# 03fpga.net
KiCad netlist of a schematic drawn in Altium Designer
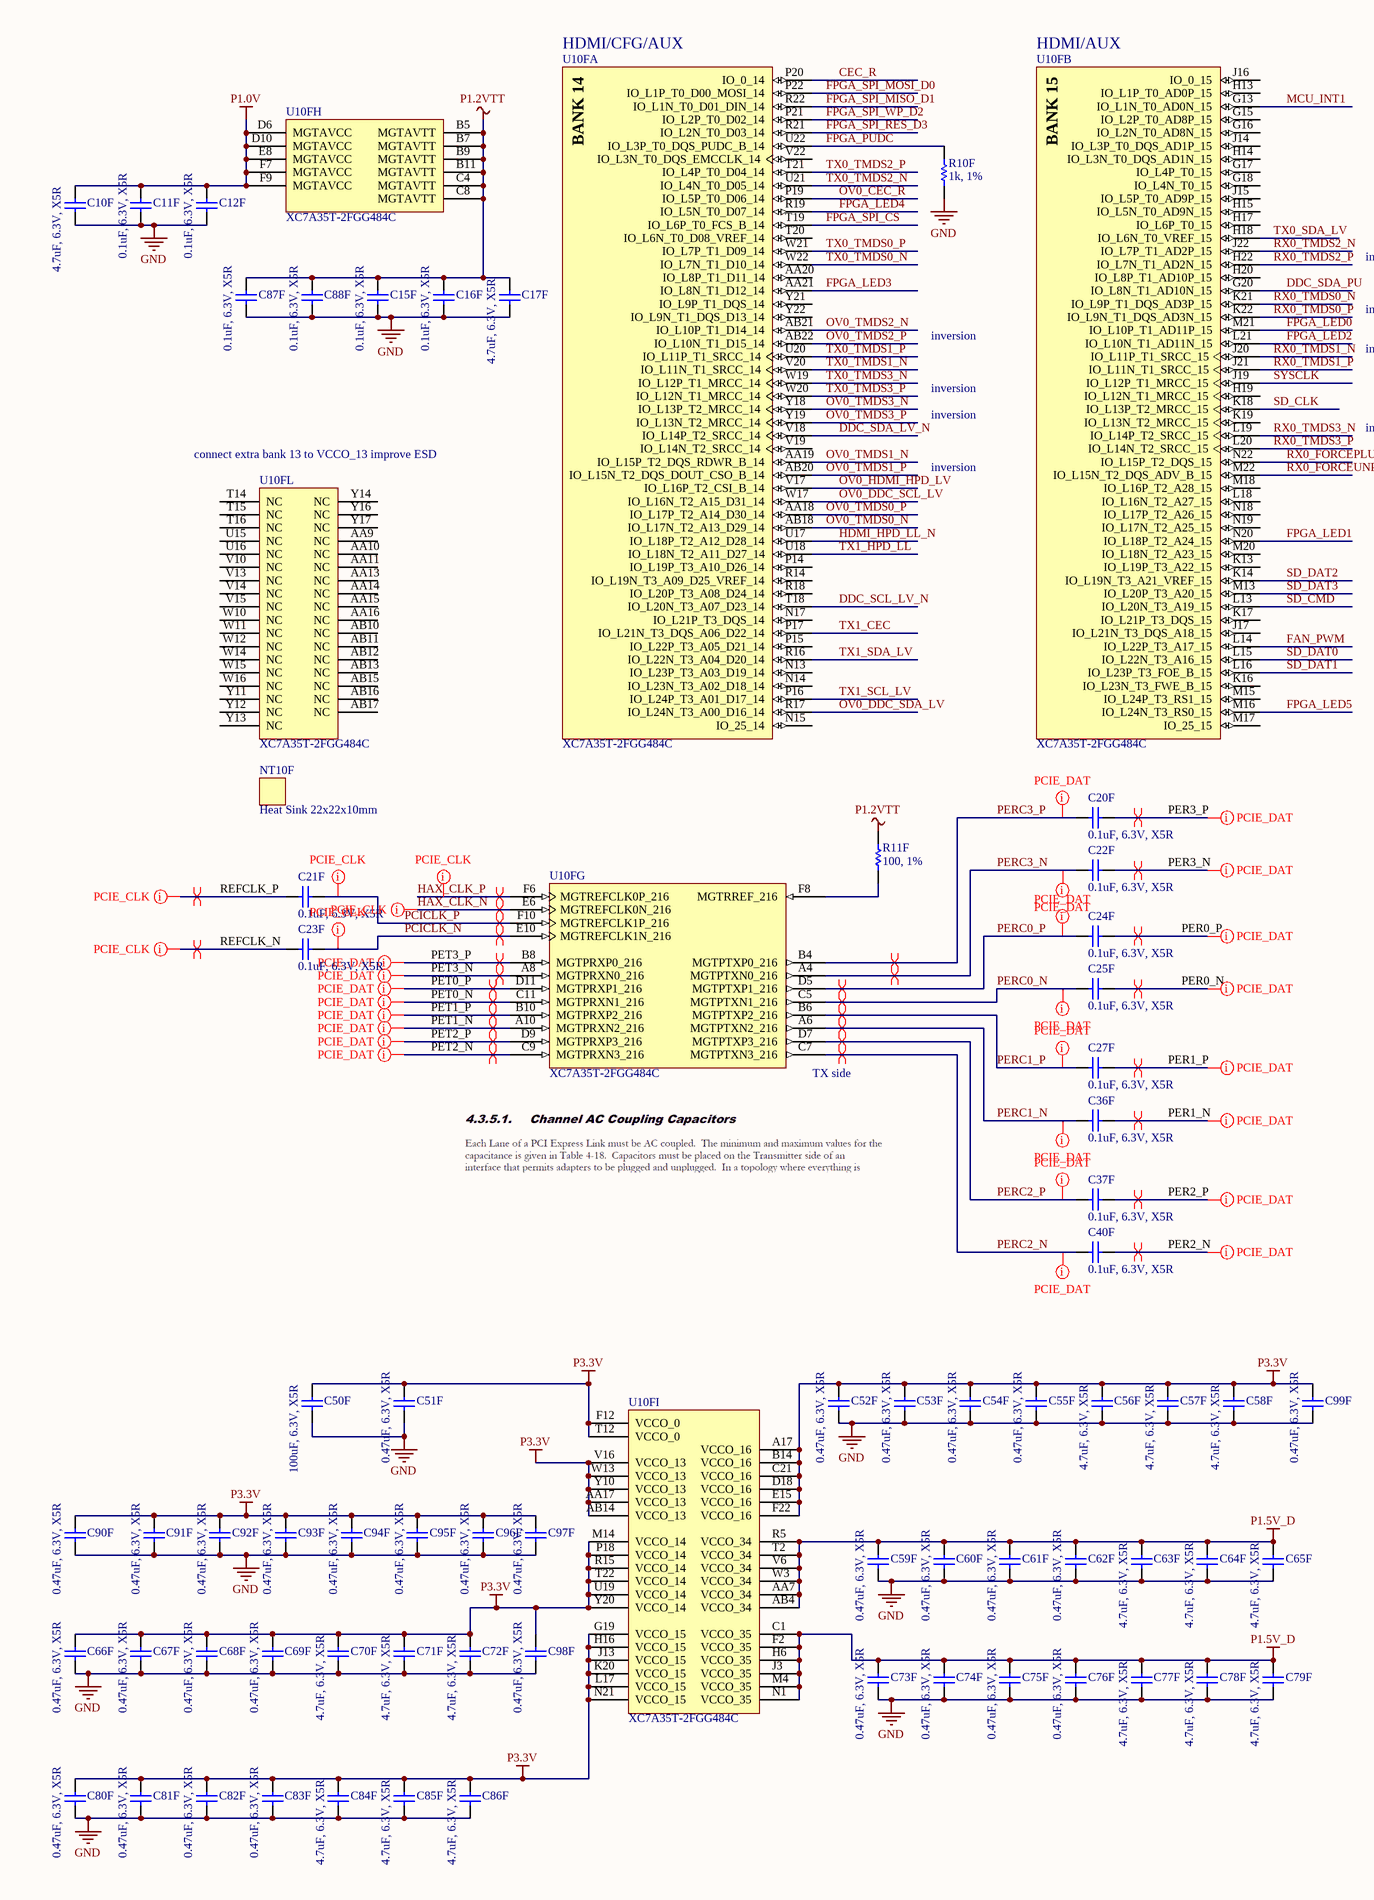
[diagram p0: 03fpga.SchDoc, left]
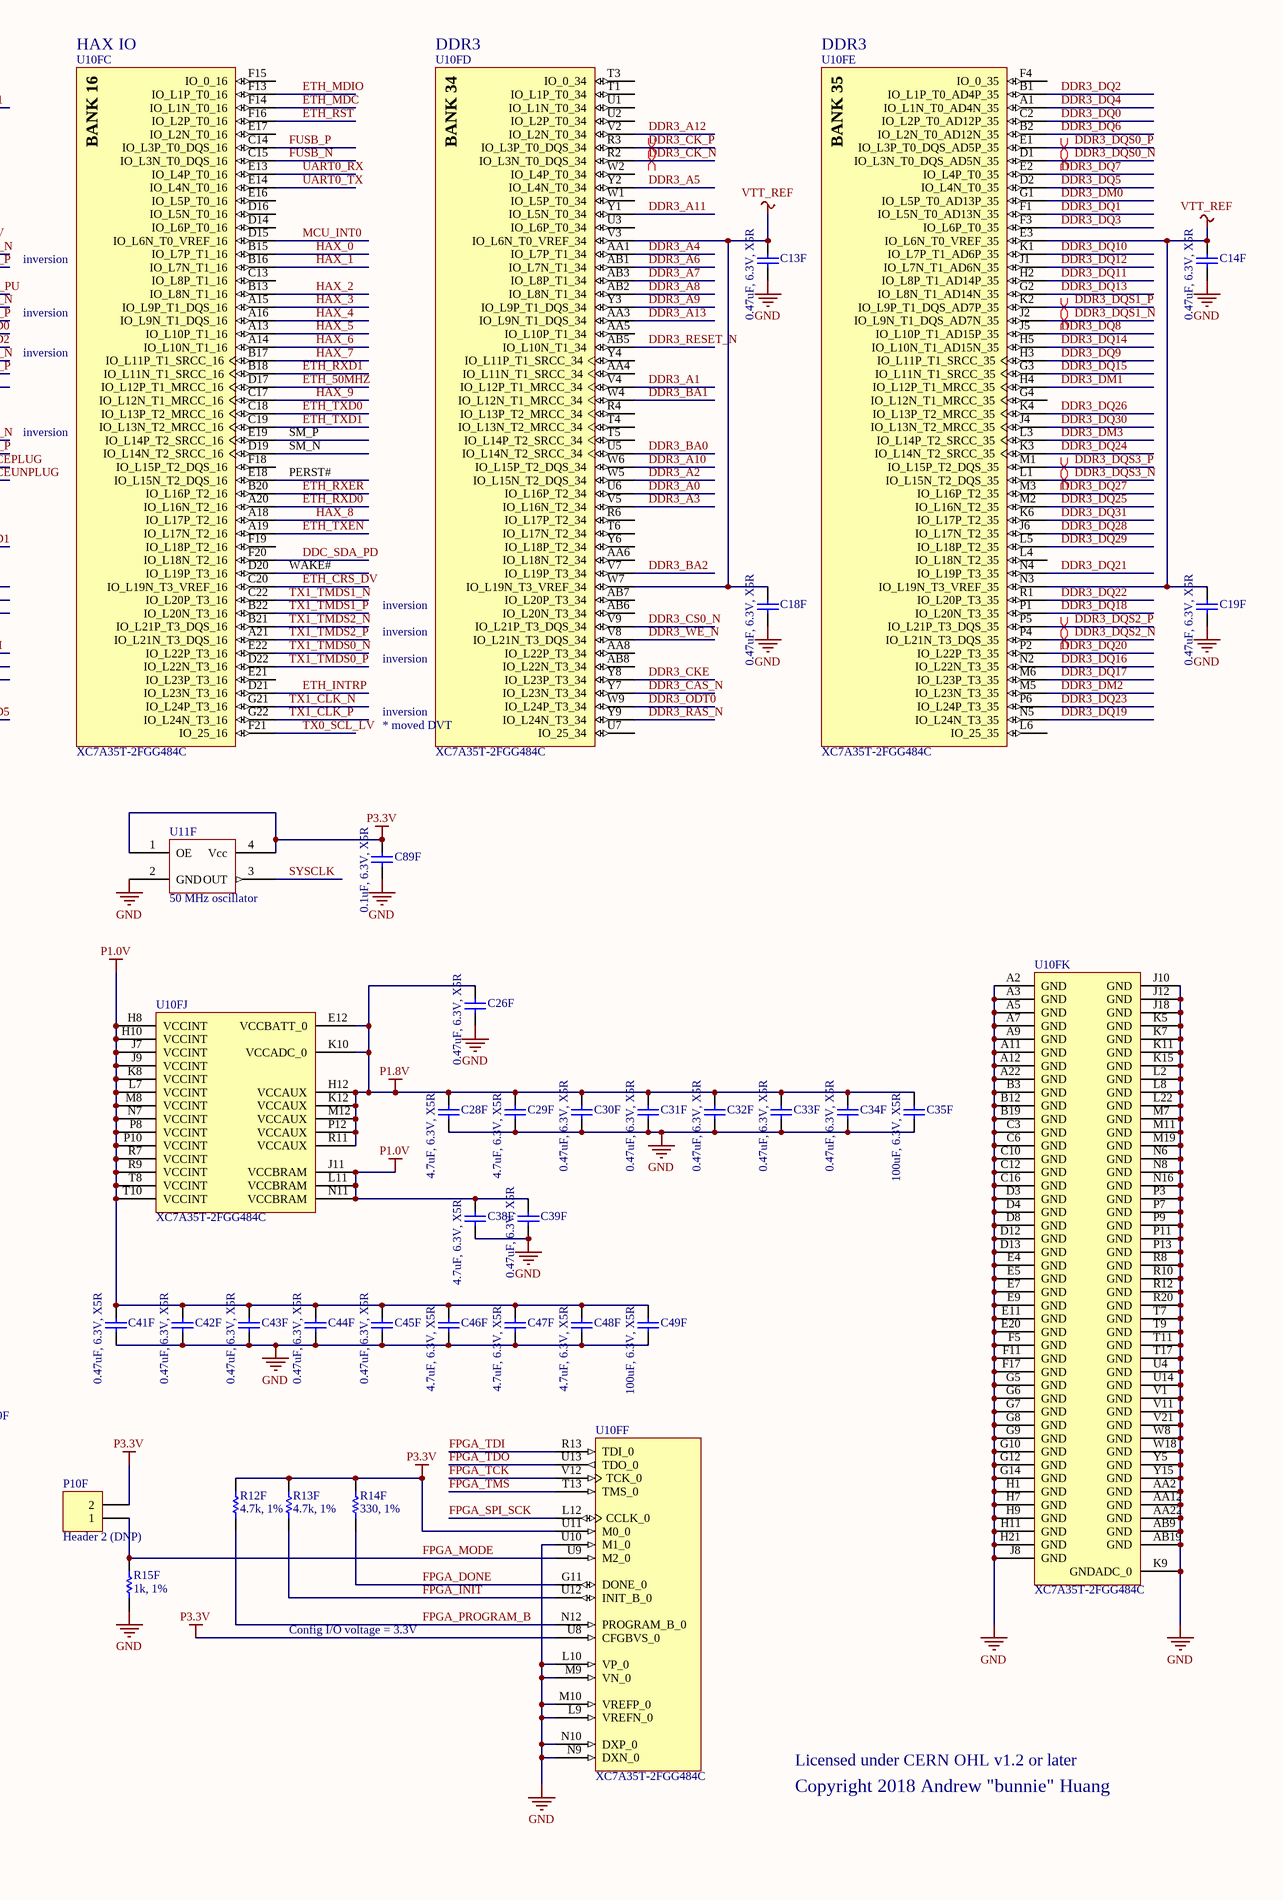
[diagram p1: 03fpga.SchDoc, right]

(export (version "E")
  (design (tool "Eeschema 10.0.6"))
  (components
    (comp (ref "C10F")
      (value "4.7uF, 6.3V, X5R")
      (footprint "CAPC1005N")
      (description "Capacitor (Semiconductor SIM Model)")
      (fields (field (name "MPN") "CL05A475MQ5NQNC"))
      (libsource (lib "Miscellaneous Devices") (part "Cap Semi"))
    )
    (comp (ref "C11F")
      (value "0.1uF, 6.3V, X5R")
      (footprint "CAPC0603X03L")
      (description "Capacitor (Semiconductor SIM Model)")
      (fields (field (name "MPN") "CL03A104KQ3NNNC"))
      (libsource (lib "Miscellaneous Devices") (part "Cap Semi"))
    )
    (comp (ref "C12F")
      (value "0.1uF, 6.3V, X5R")
      (footprint "CAPC0603X03L")
      (description "Capacitor (Semiconductor SIM Model)")
      (fields (field (name "MPN") "CL03A104KQ3NNNC"))
      (libsource (lib "Miscellaneous Devices") (part "Cap Semi"))
    )
    (comp (ref "C13F")
      (value "0.47uF, 6.3V, X5R")
      (footprint "CAPC0603X03L")
      (description "Capacitor (Semiconductor SIM Model)")
      (fields (field (name "MPN") "CL03A474KQ3NNNH"))
      (libsource (lib "Miscellaneous Devices") (part "Cap Semi"))
    )
    (comp (ref "C14F")
      (value "0.47uF, 6.3V, X5R")
      (footprint "CAPC0603X03L")
      (description "Capacitor (Semiconductor SIM Model)")
      (fields (field (name "MPN") "CL03A474KQ3NNNH"))
      (libsource (lib "Miscellaneous Devices") (part "Cap Semi"))
    )
    (comp (ref "C15F")
      (value "0.1uF, 6.3V, X5R")
      (footprint "CAPC0603X03L")
      (description "Capacitor (Semiconductor SIM Model)")
      (fields (field (name "MPN") "CL03A104KQ3NNNC"))
      (libsource (lib "Miscellaneous Devices") (part "Cap Semi"))
    )
    (comp (ref "C16F")
      (value "0.1uF, 6.3V, X5R")
      (footprint "CAPC0603X03L")
      (description "Capacitor (Semiconductor SIM Model)")
      (fields (field (name "MPN") "CL03A104KQ3NNNC"))
      (libsource (lib "Miscellaneous Devices") (part "Cap Semi"))
    )
    (comp (ref "C17F")
      (value "4.7uF, 6.3V, X5R")
      (footprint "CAPC1005N")
      (description "Capacitor (Semiconductor SIM Model)")
      (fields (field (name "MPN") "CL05A475MQ5NQNC"))
      (libsource (lib "Miscellaneous Devices") (part "Cap Semi"))
    )
    (comp (ref "C18F")
      (value "0.47uF, 6.3V, X5R")
      (footprint "CAPC0603X03L")
      (description "Capacitor (Semiconductor SIM Model)")
      (fields (field (name "MPN") "CL03A474KQ3NNNH"))
      (libsource (lib "Miscellaneous Devices") (part "Cap Semi"))
    )
    (comp (ref "C19F")
      (value "0.47uF, 6.3V, X5R")
      (footprint "CAPC0603X03L")
      (description "Capacitor (Semiconductor SIM Model)")
      (fields (field (name "MPN") "CL03A474KQ3NNNH"))
      (libsource (lib "Miscellaneous Devices") (part "Cap Semi"))
    )
    (comp (ref "C20F")
      (value "0.1uF, 6.3V, X5R")
      (footprint "CAPC0603X03L")
      (description "Capacitor (Semiconductor SIM Model)")
      (fields (field (name "MPN") "CL03A104KQ3NNNC"))
      (libsource (lib "Miscellaneous Devices") (part "Cap Semi"))
    )
    (comp (ref "C21F")
      (value "0.1uF, 6.3V, X5R")
      (footprint "CAPC0603X03L")
      (description "Capacitor (Semiconductor SIM Model)")
      (fields (field (name "MPN") "CL03A104KQ3NNNC"))
      (libsource (lib "Miscellaneous Devices") (part "Cap Semi"))
    )
    (comp (ref "C22F")
      (value "0.1uF, 6.3V, X5R")
      (footprint "CAPC0603X03L")
      (description "Capacitor (Semiconductor SIM Model)")
      (fields (field (name "MPN") "CL03A104KQ3NNNC"))
      (libsource (lib "Miscellaneous Devices") (part "Cap Semi"))
    )
    (comp (ref "C23F")
      (value "0.1uF, 6.3V, X5R")
      (footprint "CAPC0603X03L")
      (description "Capacitor (Semiconductor SIM Model)")
      (fields (field (name "MPN") "CL03A104KQ3NNNC"))
      (libsource (lib "Miscellaneous Devices") (part "Cap Semi"))
    )
    (comp (ref "C24F")
      (value "0.1uF, 6.3V, X5R")
      (footprint "CAPC0603X03L")
      (description "Capacitor (Semiconductor SIM Model)")
      (fields (field (name "MPN") "CL03A104KQ3NNNC"))
      (libsource (lib "Miscellaneous Devices") (part "Cap Semi"))
    )
    (comp (ref "C25F")
      (value "0.1uF, 6.3V, X5R")
      (footprint "CAPC0603X03L")
      (description "Capacitor (Semiconductor SIM Model)")
      (fields (field (name "MPN") "CL03A104KQ3NNNC"))
      (libsource (lib "Miscellaneous Devices") (part "Cap Semi"))
    )
    (comp (ref "C26F")
      (value "0.47uF, 6.3V, X5R")
      (footprint "CAPC0603X03L")
      (description "Capacitor (Semiconductor SIM Model)")
      (fields (field (name "MPN") "CL03A474KQ3NNNH"))
      (libsource (lib "Miscellaneous Devices") (part "Cap Semi"))
    )
    (comp (ref "C27F")
      (value "0.1uF, 6.3V, X5R")
      (footprint "CAPC0603X03L")
      (description "Capacitor (Semiconductor SIM Model)")
      (fields (field (name "MPN") "CL03A104KQ3NNNC"))
      (libsource (lib "Miscellaneous Devices") (part "Cap Semi"))
    )
    (comp (ref "C28F")
      (value "4.7uF, 6.3V, X5R")
      (footprint "CAPC1005N")
      (description "Capacitor (Semiconductor SIM Model)")
      (fields (field (name "MPN") "CL05A475MQ5NQNC"))
      (libsource (lib "Miscellaneous Devices") (part "Cap Semi"))
    )
    (comp (ref "C29F")
      (value "4.7uF, 6.3V, X5R")
      (footprint "CAPC1005N")
      (description "Capacitor (Semiconductor SIM Model)")
      (fields (field (name "MPN") "CL05A475MQ5NQNC"))
      (libsource (lib "Miscellaneous Devices") (part "Cap Semi"))
    )
    (comp (ref "C30F")
      (value "0.47uF, 6.3V, X5R")
      (footprint "CAPC0603X03L")
      (description "Capacitor (Semiconductor SIM Model)")
      (fields (field (name "MPN") "CL03A474KQ3NNNH"))
      (libsource (lib "Miscellaneous Devices") (part "Cap Semi"))
    )
    (comp (ref "C31F")
      (value "0.47uF, 6.3V, X5R")
      (footprint "CAPC0603X03L")
      (description "Capacitor (Semiconductor SIM Model)")
      (fields (field (name "MPN") "CL03A474KQ3NNNH"))
      (libsource (lib "Miscellaneous Devices") (part "Cap Semi"))
    )
    (comp (ref "C32F")
      (value "0.47uF, 6.3V, X5R")
      (footprint "CAPC0603X03L")
      (description "Capacitor (Semiconductor SIM Model)")
      (fields (field (name "MPN") "CL03A474KQ3NNNH"))
      (libsource (lib "Miscellaneous Devices") (part "Cap Semi"))
    )
    (comp (ref "C33F")
      (value "0.47uF, 6.3V, X5R")
      (footprint "CAPC0603X03L")
      (description "Capacitor (Semiconductor SIM Model)")
      (fields (field (name "MPN") "CL03A474KQ3NNNH"))
      (libsource (lib "Miscellaneous Devices") (part "Cap Semi"))
    )
    (comp (ref "C34F")
      (value "0.47uF, 6.3V, X5R")
      (footprint "CAPC0603X03L")
      (description "Capacitor (Semiconductor SIM Model)")
      (fields (field (name "MPN") "CL03A474KQ3NNNH"))
      (libsource (lib "Miscellaneous Devices") (part "Cap Semi"))
    )
    (comp (ref "C35F")
      (value "100uF, 6.3V, X5R")
      (footprint "CAPC3216N")
      (description "Capacitor (Semiconductor SIM Model)")
      (fields (field (name "MPN") "CL31A107MQHNNNE"))
      (libsource (lib "Miscellaneous Devices") (part "Cap Semi"))
    )
    (comp (ref "C36F")
      (value "0.1uF, 6.3V, X5R")
      (footprint "CAPC0603X03L")
      (description "Capacitor (Semiconductor SIM Model)")
      (fields (field (name "MPN") "CL03A104KQ3NNNC"))
      (libsource (lib "Miscellaneous Devices") (part "Cap Semi"))
    )
    (comp (ref "C37F")
      (value "0.1uF, 6.3V, X5R")
      (footprint "CAPC0603X03L")
      (description "Capacitor (Semiconductor SIM Model)")
      (fields (field (name "MPN") "CL03A104KQ3NNNC"))
      (libsource (lib "Miscellaneous Devices") (part "Cap Semi"))
    )
    (comp (ref "C38F")
      (value "4.7uF, 6.3V, X5R")
      (footprint "CAPC1005N")
      (description "Capacitor (Semiconductor SIM Model)")
      (fields (field (name "MPN") "CL05A475MQ5NQNC"))
      (libsource (lib "Miscellaneous Devices") (part "Cap Semi"))
    )
    (comp (ref "C39F")
      (value "0.47uF, 6.3V, X5R")
      (footprint "CAPC0603X03L")
      (description "Capacitor (Semiconductor SIM Model)")
      (fields (field (name "MPN") "CL03A474KQ3NNNH"))
      (libsource (lib "Miscellaneous Devices") (part "Cap Semi"))
    )
    (comp (ref "C40F")
      (value "0.1uF, 6.3V, X5R")
      (footprint "CAPC0603X03L")
      (description "Capacitor (Semiconductor SIM Model)")
      (fields (field (name "MPN") "CL03A104KQ3NNNC"))
      (libsource (lib "Miscellaneous Devices") (part "Cap Semi"))
    )
    (comp (ref "C41F")
      (value "0.47uF, 6.3V, X5R")
      (footprint "CAPC0603X03L")
      (description "Capacitor (Semiconductor SIM Model)")
      (fields (field (name "MPN") "CL03A474KQ3NNNH"))
      (libsource (lib "Miscellaneous Devices") (part "Cap Semi"))
    )
    (comp (ref "C42F")
      (value "0.47uF, 6.3V, X5R")
      (footprint "CAPC0603X03L")
      (description "Capacitor (Semiconductor SIM Model)")
      (fields (field (name "MPN") "CL03A474KQ3NNNH"))
      (libsource (lib "Miscellaneous Devices") (part "Cap Semi"))
    )
    (comp (ref "C43F")
      (value "0.47uF, 6.3V, X5R")
      (footprint "CAPC0603X03L")
      (description "Capacitor (Semiconductor SIM Model)")
      (fields (field (name "MPN") "CL03A474KQ3NNNH"))
      (libsource (lib "Miscellaneous Devices") (part "Cap Semi"))
    )
    (comp (ref "C44F")
      (value "0.47uF, 6.3V, X5R")
      (footprint "CAPC0603X03L")
      (description "Capacitor (Semiconductor SIM Model)")
      (fields (field (name "MPN") "CL03A474KQ3NNNH"))
      (libsource (lib "Miscellaneous Devices") (part "Cap Semi"))
    )
    (comp (ref "C45F")
      (value "0.47uF, 6.3V, X5R")
      (footprint "CAPC0603X03L")
      (description "Capacitor (Semiconductor SIM Model)")
      (fields (field (name "MPN") "CL03A474KQ3NNNH"))
      (libsource (lib "Miscellaneous Devices") (part "Cap Semi"))
    )
    (comp (ref "C46F")
      (value "4.7uF, 6.3V, X5R")
      (footprint "CAPC1005N")
      (description "Capacitor (Semiconductor SIM Model)")
      (fields (field (name "MPN") "CL05A475MQ5NQNC"))
      (libsource (lib "Miscellaneous Devices") (part "Cap Semi"))
    )
    (comp (ref "C47F")
      (value "4.7uF, 6.3V, X5R")
      (footprint "CAPC1005N")
      (description "Capacitor (Semiconductor SIM Model)")
      (fields (field (name "MPN") "CL05A475MQ5NQNC"))
      (libsource (lib "Miscellaneous Devices") (part "Cap Semi"))
    )
    (comp (ref "C48F")
      (value "4.7uF, 6.3V, X5R")
      (footprint "CAPC1005N")
      (description "Capacitor (Semiconductor SIM Model)")
      (fields (field (name "MPN") "CL05A475MQ5NQNC"))
      (libsource (lib "Miscellaneous Devices") (part "Cap Semi"))
    )
    (comp (ref "C49F")
      (value "100uF, 6.3V, X5R")
      (footprint "CAPC3216N")
      (description "Capacitor (Semiconductor SIM Model)")
      (fields (field (name "MPN") "CL31A107MQHNNNE"))
      (libsource (lib "Miscellaneous Devices") (part "Cap Semi"))
    )
    (comp (ref "C50F")
      (value "100uF, 6.3V, X5R")
      (footprint "CAPC3216N")
      (description "Capacitor (Semiconductor SIM Model)")
      (fields (field (name "MPN") "CL31A107MQHNNNE"))
      (libsource (lib "Miscellaneous Devices") (part "Cap Semi"))
    )
    (comp (ref "C51F")
      (value "0.47uF, 6.3V, X5R")
      (footprint "CAPC0603X03L")
      (description "Capacitor (Semiconductor SIM Model)")
      (fields (field (name "MPN") "CL03A474KQ3NNNH"))
      (libsource (lib "Miscellaneous Devices") (part "Cap Semi"))
    )
    (comp (ref "C52F")
      (value "0.47uF, 6.3V, X5R")
      (footprint "CAPC0603X03L")
      (description "Capacitor (Semiconductor SIM Model)")
      (fields (field (name "MPN") "CL03A474KQ3NNNH"))
      (libsource (lib "Miscellaneous Devices") (part "Cap Semi"))
    )
    (comp (ref "C53F")
      (value "0.47uF, 6.3V, X5R")
      (footprint "CAPC0603X03L")
      (description "Capacitor (Semiconductor SIM Model)")
      (fields (field (name "MPN") "CL03A474KQ3NNNH"))
      (libsource (lib "Miscellaneous Devices") (part "Cap Semi"))
    )
    (comp (ref "C54F")
      (value "0.47uF, 6.3V, X5R")
      (footprint "CAPC0603X03L")
      (description "Capacitor (Semiconductor SIM Model)")
      (fields (field (name "MPN") "CL03A474KQ3NNNH"))
      (libsource (lib "Miscellaneous Devices") (part "Cap Semi"))
    )
    (comp (ref "C55F")
      (value "0.47uF, 6.3V, X5R")
      (footprint "CAPC0603X03L")
      (description "Capacitor (Semiconductor SIM Model)")
      (fields (field (name "MPN") "CL03A474KQ3NNNH"))
      (libsource (lib "Miscellaneous Devices") (part "Cap Semi"))
    )
    (comp (ref "C56F")
      (value "4.7uF, 6.3V, X5R")
      (footprint "CAPC1005N")
      (description "Capacitor (Semiconductor SIM Model)")
      (fields (field (name "MPN") "CL05A475MQ5NQNC"))
      (libsource (lib "Miscellaneous Devices") (part "Cap Semi"))
    )
    (comp (ref "C57F")
      (value "4.7uF, 6.3V, X5R")
      (footprint "CAPC1005N")
      (description "Capacitor (Semiconductor SIM Model)")
      (fields (field (name "MPN") "CL05A475MQ5NQNC"))
      (libsource (lib "Miscellaneous Devices") (part "Cap Semi"))
    )
    (comp (ref "C58F")
      (value "4.7uF, 6.3V, X5R")
      (footprint "CAPC1005N")
      (description "Capacitor (Semiconductor SIM Model)")
      (fields (field (name "MPN") "CL05A475MQ5NQNC"))
      (libsource (lib "Miscellaneous Devices") (part "Cap Semi"))
    )
    (comp (ref "C59F")
      (value "0.47uF, 6.3V, X5R")
      (footprint "CAPC0603X03L")
      (description "Capacitor (Semiconductor SIM Model)")
      (fields (field (name "MPN") "CL03A474KQ3NNNH"))
      (libsource (lib "Miscellaneous Devices") (part "Cap Semi"))
    )
    (comp (ref "C60F")
      (value "0.47uF, 6.3V, X5R")
      (footprint "CAPC0603X03L")
      (description "Capacitor (Semiconductor SIM Model)")
      (fields (field (name "MPN") "CL03A474KQ3NNNH"))
      (libsource (lib "Miscellaneous Devices") (part "Cap Semi"))
    )
    (comp (ref "C61F")
      (value "0.47uF, 6.3V, X5R")
      (footprint "CAPC0603X03L")
      (description "Capacitor (Semiconductor SIM Model)")
      (fields (field (name "MPN") "CL03A474KQ3NNNH"))
      (libsource (lib "Miscellaneous Devices") (part "Cap Semi"))
    )
    (comp (ref "C62F")
      (value "0.47uF, 6.3V, X5R")
      (footprint "CAPC0603X03L")
      (description "Capacitor (Semiconductor SIM Model)")
      (fields (field (name "MPN") "CL03A474KQ3NNNH"))
      (libsource (lib "Miscellaneous Devices") (part "Cap Semi"))
    )
    (comp (ref "C63F")
      (value "4.7uF, 6.3V, X5R")
      (footprint "CAPC1005N")
      (description "Capacitor (Semiconductor SIM Model)")
      (fields (field (name "MPN") "CL05A475MQ5NQNC"))
      (libsource (lib "Miscellaneous Devices") (part "Cap Semi"))
    )
    (comp (ref "C64F")
      (value "4.7uF, 6.3V, X5R")
      (footprint "CAPC1005N")
      (description "Capacitor (Semiconductor SIM Model)")
      (fields (field (name "MPN") "CL05A475MQ5NQNC"))
      (libsource (lib "Miscellaneous Devices") (part "Cap Semi"))
    )
    (comp (ref "C65F")
      (value "4.7uF, 6.3V, X5R")
      (footprint "CAPC1005N")
      (description "Capacitor (Semiconductor SIM Model)")
      (fields (field (name "MPN") "CL05A475MQ5NQNC"))
      (libsource (lib "Miscellaneous Devices") (part "Cap Semi"))
    )
    (comp (ref "C66F")
      (value "0.47uF, 6.3V, X5R")
      (footprint "CAPC0603X03L")
      (description "Capacitor (Semiconductor SIM Model)")
      (fields (field (name "MPN") "CL03A474KQ3NNNH"))
      (libsource (lib "Miscellaneous Devices") (part "Cap Semi"))
    )
    (comp (ref "C67F")
      (value "0.47uF, 6.3V, X5R")
      (footprint "CAPC0603X03L")
      (description "Capacitor (Semiconductor SIM Model)")
      (fields (field (name "MPN") "CL03A474KQ3NNNH"))
      (libsource (lib "Miscellaneous Devices") (part "Cap Semi"))
    )
    (comp (ref "C68F")
      (value "0.47uF, 6.3V, X5R")
      (footprint "CAPC0603X03L")
      (description "Capacitor (Semiconductor SIM Model)")
      (fields (field (name "MPN") "CL03A474KQ3NNNH"))
      (libsource (lib "Miscellaneous Devices") (part "Cap Semi"))
    )
    (comp (ref "C69F")
      (value "0.47uF, 6.3V, X5R")
      (footprint "CAPC0603X03L")
      (description "Capacitor (Semiconductor SIM Model)")
      (fields (field (name "MPN") "CL03A474KQ3NNNH"))
      (libsource (lib "Miscellaneous Devices") (part "Cap Semi"))
    )
    (comp (ref "C70F")
      (value "4.7uF, 6.3V, X5R")
      (footprint "CAPC1005N")
      (description "Capacitor (Semiconductor SIM Model)")
      (fields (field (name "MPN") "CL05A475MQ5NQNC"))
      (libsource (lib "Miscellaneous Devices") (part "Cap Semi"))
    )
    (comp (ref "C71F")
      (value "4.7uF, 6.3V, X5R")
      (footprint "CAPC1005N")
      (description "Capacitor (Semiconductor SIM Model)")
      (fields (field (name "MPN") "CL05A475MQ5NQNC"))
      (libsource (lib "Miscellaneous Devices") (part "Cap Semi"))
    )
    (comp (ref "C72F")
      (value "4.7uF, 6.3V, X5R")
      (footprint "CAPC1005N")
      (description "Capacitor (Semiconductor SIM Model)")
      (fields (field (name "MPN") "CL05A475MQ5NQNC"))
      (libsource (lib "Miscellaneous Devices") (part "Cap Semi"))
    )
    (comp (ref "C73F")
      (value "0.47uF, 6.3V, X5R")
      (footprint "CAPC0603X03L")
      (description "Capacitor (Semiconductor SIM Model)")
      (fields (field (name "MPN") "CL03A474KQ3NNNH"))
      (libsource (lib "Miscellaneous Devices") (part "Cap Semi"))
    )
    (comp (ref "C74F")
      (value "0.47uF, 6.3V, X5R")
      (footprint "CAPC0603X03L")
      (description "Capacitor (Semiconductor SIM Model)")
      (fields (field (name "MPN") "CL03A474KQ3NNNH"))
      (libsource (lib "Miscellaneous Devices") (part "Cap Semi"))
    )
    (comp (ref "C75F")
      (value "0.47uF, 6.3V, X5R")
      (footprint "CAPC0603X03L")
      (description "Capacitor (Semiconductor SIM Model)")
      (fields (field (name "MPN") "CL03A474KQ3NNNH"))
      (libsource (lib "Miscellaneous Devices") (part "Cap Semi"))
    )
    (comp (ref "C76F")
      (value "0.47uF, 6.3V, X5R")
      (footprint "CAPC0603X03L")
      (description "Capacitor (Semiconductor SIM Model)")
      (fields (field (name "MPN") "CL03A474KQ3NNNH"))
      (libsource (lib "Miscellaneous Devices") (part "Cap Semi"))
    )
    (comp (ref "C77F")
      (value "4.7uF, 6.3V, X5R")
      (footprint "CAPC1005N")
      (description "Capacitor (Semiconductor SIM Model)")
      (fields (field (name "MPN") "CL05A475MQ5NQNC"))
      (libsource (lib "Miscellaneous Devices") (part "Cap Semi"))
    )
    (comp (ref "C78F")
      (value "4.7uF, 6.3V, X5R")
      (footprint "CAPC1005N")
      (description "Capacitor (Semiconductor SIM Model)")
      (fields (field (name "MPN") "CL05A475MQ5NQNC"))
      (libsource (lib "Miscellaneous Devices") (part "Cap Semi"))
    )
    (comp (ref "C79F")
      (value "4.7uF, 6.3V, X5R")
      (footprint "CAPC1005N")
      (description "Capacitor (Semiconductor SIM Model)")
      (fields (field (name "MPN") "CL05A475MQ5NQNC"))
      (libsource (lib "Miscellaneous Devices") (part "Cap Semi"))
    )
    (comp (ref "C80F")
      (value "0.47uF, 6.3V, X5R")
      (footprint "CAPC0603X03L")
      (description "Capacitor (Semiconductor SIM Model)")
      (fields (field (name "MPN") "CL03A474KQ3NNNH"))
      (libsource (lib "Miscellaneous Devices") (part "Cap Semi"))
    )
    (comp (ref "C81F")
      (value "0.47uF, 6.3V, X5R")
      (footprint "CAPC0603X03L")
      (description "Capacitor (Semiconductor SIM Model)")
      (fields (field (name "MPN") "CL03A474KQ3NNNH"))
      (libsource (lib "Miscellaneous Devices") (part "Cap Semi"))
    )
    (comp (ref "C82F")
      (value "0.47uF, 6.3V, X5R")
      (footprint "CAPC0603X03L")
      (description "Capacitor (Semiconductor SIM Model)")
      (fields (field (name "MPN") "CL03A474KQ3NNNH"))
      (libsource (lib "Miscellaneous Devices") (part "Cap Semi"))
    )
    (comp (ref "C83F")
      (value "0.47uF, 6.3V, X5R")
      (footprint "CAPC0603X03L")
      (description "Capacitor (Semiconductor SIM Model)")
      (fields (field (name "MPN") "CL03A474KQ3NNNH"))
      (libsource (lib "Miscellaneous Devices") (part "Cap Semi"))
    )
    (comp (ref "C84F")
      (value "4.7uF, 6.3V, X5R")
      (footprint "CAPC1005N")
      (description "Capacitor (Semiconductor SIM Model)")
      (fields (field (name "MPN") "CL05A475MQ5NQNC"))
      (libsource (lib "Miscellaneous Devices") (part "Cap Semi"))
    )
    (comp (ref "C85F")
      (value "4.7uF, 6.3V, X5R")
      (footprint "CAPC1005N")
      (description "Capacitor (Semiconductor SIM Model)")
      (fields (field (name "MPN") "CL05A475MQ5NQNC"))
      (libsource (lib "Miscellaneous Devices") (part "Cap Semi"))
    )
    (comp (ref "C86F")
      (value "4.7uF, 6.3V, X5R")
      (footprint "CAPC1005N")
      (description "Capacitor (Semiconductor SIM Model)")
      (fields (field (name "MPN") "CL05A475MQ5NQNC"))
      (libsource (lib "Miscellaneous Devices") (part "Cap Semi"))
    )
    (comp (ref "C87F")
      (value "0.1uF, 6.3V, X5R")
      (footprint "CAPC0603X03L")
      (description "Capacitor (Semiconductor SIM Model)")
      (fields (field (name "MPN") "CL03A104KQ3NNNC"))
      (libsource (lib "Miscellaneous Devices") (part "Cap Semi"))
    )
    (comp (ref "C88F")
      (value "0.1uF, 6.3V, X5R")
      (footprint "CAPC0603X03L")
      (description "Capacitor (Semiconductor SIM Model)")
      (fields (field (name "MPN") "CL03A104KQ3NNNC"))
      (libsource (lib "Miscellaneous Devices") (part "Cap Semi"))
    )
    (comp (ref "C89F")
      (value "0.1uF, 6.3V, X5R")
      (footprint "CAPC0603X03L")
      (description "Capacitor (Semiconductor SIM Model)")
      (fields (field (name "MPN") "CL03A104KQ3NNNC"))
      (libsource (lib "Miscellaneous Devices") (part "Cap Semi"))
    )
    (comp (ref "C90F")
      (value "0.47uF, 6.3V, X5R")
      (footprint "CAPC0603X03L")
      (description "Capacitor (Semiconductor SIM Model)")
      (fields (field (name "MPN") "CL03A474KQ3NNNH"))
      (libsource (lib "Miscellaneous Devices") (part "Cap Semi"))
    )
    (comp (ref "C91F")
      (value "0.47uF, 6.3V, X5R")
      (footprint "CAPC0603X03L")
      (description "Capacitor (Semiconductor SIM Model)")
      (fields (field (name "MPN") "CL03A474KQ3NNNH"))
      (libsource (lib "Miscellaneous Devices") (part "Cap Semi"))
    )
    (comp (ref "C92F")
      (value "0.47uF, 6.3V, X5R")
      (footprint "CAPC0603X03L")
      (description "Capacitor (Semiconductor SIM Model)")
      (fields (field (name "MPN") "CL03A474KQ3NNNH"))
      (libsource (lib "Miscellaneous Devices") (part "Cap Semi"))
    )
    (comp (ref "C93F")
      (value "0.47uF, 6.3V, X5R")
      (footprint "CAPC0603X03L")
      (description "Capacitor (Semiconductor SIM Model)")
      (fields (field (name "MPN") "CL03A474KQ3NNNH"))
      (libsource (lib "Miscellaneous Devices") (part "Cap Semi"))
    )
    (comp (ref "C94F")
      (value "0.47uF, 6.3V, X5R")
      (footprint "CAPC0603X03L")
      (description "Capacitor (Semiconductor SIM Model)")
      (fields (field (name "MPN") "CL03A474KQ3NNNH"))
      (libsource (lib "Miscellaneous Devices") (part "Cap Semi"))
    )
    (comp (ref "C95F")
      (value "0.47uF, 6.3V, X5R")
      (footprint "CAPC0603X03L")
      (description "Capacitor (Semiconductor SIM Model)")
      (fields (field (name "MPN") "CL03A474KQ3NNNH"))
      (libsource (lib "Miscellaneous Devices") (part "Cap Semi"))
    )
    (comp (ref "C96F")
      (value "0.47uF, 6.3V, X5R")
      (footprint "CAPC0603X03L")
      (description "Capacitor (Semiconductor SIM Model)")
      (fields (field (name "MPN") "CL03A474KQ3NNNH"))
      (libsource (lib "Miscellaneous Devices") (part "Cap Semi"))
    )
    (comp (ref "C97F")
      (value "0.47uF, 6.3V, X5R")
      (footprint "CAPC0603X03L")
      (description "Capacitor (Semiconductor SIM Model)")
      (fields (field (name "MPN") "CL03A474KQ3NNNH"))
      (libsource (lib "Miscellaneous Devices") (part "Cap Semi"))
    )
    (comp (ref "C98F")
      (value "0.47uF, 6.3V, X5R")
      (footprint "CAPC0603X03L")
      (description "Capacitor (Semiconductor SIM Model)")
      (fields (field (name "MPN") "CL03A474KQ3NNNH"))
      (libsource (lib "Miscellaneous Devices") (part "Cap Semi"))
    )
    (comp (ref "C99F")
      (value "0.47uF, 6.3V, X5R")
      (footprint "CAPC0603X03L")
      (description "Capacitor (Semiconductor SIM Model)")
      (fields (field (name "MPN") "CL03A474KQ3NNNH"))
      (libsource (lib "Miscellaneous Devices") (part "Cap Semi"))
    )
    (comp (ref "NT10F")
      (value "Heat Sink 22x22x10mm")
      (description "Placeholder for non-board BOM items")
      (fields (field (name "MPN") "22x22x10mm heat sink + double tape"))
      (libsource (lib "commonsch") (part "NOTE"))
    )
    (comp (ref "P10F")
      (value "Header 2 (DNP)")
      (footprint "HDR1X2")
      (description "Header, 2-Pin")
      (fields (field (name "MPN") "DNP") (field (name "PUBLISHER") "Altium Limited"))
      (libsource (lib "Miscellaneous Connectors") (part "Header 2"))
    )
    (comp (ref "R10F")
      (value "1k, 1%")
      (footprint "RESC1005N")
      (description "Resistor")
      (fields (field (name "MPN") "RS02U102FT"))
      (libsource (lib "Miscellaneous Devices") (part "Res1"))
    )
    (comp (ref "R11F")
      (value "100, 1%")
      (footprint "RESC1005N")
      (description "Resistor")
      (fields (field (name "MPN") "ANY"))
      (libsource (lib "Miscellaneous Devices") (part "Res1"))
    )
    (comp (ref "R12F")
      (value "4.7k, 1%")
      (footprint "RESC1005N")
      (description "Resistor")
      (fields (field (name "MPN") "ANY"))
      (libsource (lib "Miscellaneous Devices") (part "Res1"))
    )
    (comp (ref "R13F")
      (value "4.7k, 1%")
      (footprint "RESC1005N")
      (description "Resistor")
      (fields (field (name "MPN") "ANY"))
      (libsource (lib "Miscellaneous Devices") (part "Res1"))
    )
    (comp (ref "R14F")
      (value "330, 1%")
      (footprint "RESC1005N")
      (description "Resistor")
      (fields (field (name "MPN") "RS02U331FT"))
      (libsource (lib "Miscellaneous Devices") (part "Res1"))
    )
    (comp (ref "R15F")
      (value "1k, 1%")
      (footprint "RESC1005N")
      (description "Resistor")
      (fields (field (name "MPN") "RS02U102FT"))
      (libsource (lib "Miscellaneous Devices") (part "Res1"))
    )
    (comp (ref "U10F")
      (value "XC7A35T-2FGG484C")
      (footprint "FGG484")
      (description "Artix-7 FPGA, 250 User I/Os, 4 GTP, 484-Ball BGA, Speed Grade 2, Commercial Grade, Pb-Free")
      (fields (field (name "MANUFACTURER") "Xilinx"))
      (libsource (lib "Xilinx Artix-7") (part "XC7A35T-2FGG484C"))
    )
    (comp (ref "U11F")
      (value "50 MHz oscillator")
      (footprint "ABRACON_ASDMB")
      (description "Abracon ASDMB Miniature Oscillator")
      (fields (field (name "MPN") "ASDMB-50.000MHZ-LC-T"))
      (libsource (lib "commonsch") (part "OSCILLATOR"))
    )
  )
  (nets
    (net (code "1") (name "/CEC_R") (class "Default")
      (node (ref "U10F") (pin "P20") (pinfunction "IO_0_14_P20") (pintype "bidirectional"))
    )
    (net (code "2") (name "/DDC_SCL_LV_N") (class "Default")
      (node (ref "U10F") (pin "T18") (pinfunction "IO_L20N_T3_A07_D23_14_T18") (pintype "bidirectional"))
    )
    (net (code "3") (name "/DDC_SDA_LV_N") (class "Default")
      (node (ref "U10F") (pin "V18") (pinfunction "IO_L14P_T2_SRCC_14_V18") (pintype "bidirectional"))
    )
    (net (code "4") (name "/DDC_SDA_PD") (class "Default")
      (node (ref "U10F") (pin "F20") (pinfunction "IO_L18N_T2_16_F20") (pintype "bidirectional"))
    )
    (net (code "5") (name "/DDC_SDA_PU") (class "Default")
      (node (ref "U10F") (pin "G20") (pinfunction "IO_L8N_T1_AD10N_15_G20") (pintype "bidirectional"))
    )
    (net (code "6") (name "/DDR3_A0") (class "Default")
      (node (ref "U10F") (pin "U6") (pinfunction "IO_L16P_T2_34_U6") (pintype "bidirectional"))
    )
    (net (code "7") (name "/DDR3_A1") (class "Default")
      (node (ref "U10F") (pin "V4") (pinfunction "IO_L12P_T1_MRCC_34_V4") (pintype "bidirectional"))
    )
    (net (code "8") (name "/DDR3_A2") (class "Default")
      (node (ref "U10F") (pin "W5") (pinfunction "IO_L15N_T2_DQS_34_W5") (pintype "bidirectional"))
    )
    (net (code "9") (name "/DDR3_A3") (class "Default")
      (node (ref "U10F") (pin "V5") (pinfunction "IO_L16N_T2_34_V5") (pintype "bidirectional"))
    )
    (net (code "10") (name "/DDR3_A4") (class "Default")
      (node (ref "U10F") (pin "AA1") (pinfunction "IO_L7P_T1_34_AA1") (pintype "bidirectional"))
    )
    (net (code "11") (name "/DDR3_A5") (class "Default")
      (node (ref "U10F") (pin "Y2") (pinfunction "IO_L4N_T0_34_Y2") (pintype "bidirectional"))
    )
    (net (code "12") (name "/DDR3_A6") (class "Default")
      (node (ref "U10F") (pin "AB1") (pinfunction "IO_L7N_T1_34_AB1") (pintype "bidirectional"))
    )
    (net (code "13") (name "/DDR3_A7") (class "Default")
      (node (ref "U10F") (pin "AB3") (pinfunction "IO_L8P_T1_34_AB3") (pintype "bidirectional"))
    )
    (net (code "14") (name "/DDR3_A8") (class "Default")
      (node (ref "U10F") (pin "AB2") (pinfunction "IO_L8N_T1_34_AB2") (pintype "bidirectional"))
    )
    (net (code "15") (name "/DDR3_A9") (class "Default")
      (node (ref "U10F") (pin "Y3") (pinfunction "IO_L9P_T1_DQS_34_Y3") (pintype "bidirectional"))
    )
    (net (code "16") (name "/DDR3_A10") (class "Default")
      (node (ref "U10F") (pin "W6") (pinfunction "IO_L15P_T2_DQS_34_W6") (pintype "bidirectional"))
    )
    (net (code "17") (name "/DDR3_A11") (class "Default")
      (node (ref "U10F") (pin "Y1") (pinfunction "IO_L5N_T0_34_Y1") (pintype "bidirectional"))
    )
    (net (code "18") (name "/DDR3_A12") (class "Default")
      (node (ref "U10F") (pin "V2") (pinfunction "IO_L2N_T0_34_V2") (pintype "bidirectional"))
    )
    (net (code "19") (name "/DDR3_A13") (class "Default")
      (node (ref "U10F") (pin "AA3") (pinfunction "IO_L9N_T1_DQS_34_AA3") (pintype "bidirectional"))
    )
    (net (code "20") (name "/DDR3_BA0") (class "Default")
      (node (ref "U10F") (pin "U5") (pinfunction "IO_L14N_T2_SRCC_34_U5") (pintype "bidirectional"))
    )
    (net (code "21") (name "/DDR3_BA1") (class "Default")
      (node (ref "U10F") (pin "W4") (pinfunction "IO_L12N_T1_MRCC_34_W4") (pintype "bidirectional"))
    )
    (net (code "22") (name "/DDR3_BA2") (class "Default")
      (node (ref "U10F") (pin "V7") (pinfunction "IO_L19P_T3_34_V7") (pintype "bidirectional"))
    )
    (net (code "23") (name "/DDR3_CAS_N") (class "Default")
      (node (ref "U10F") (pin "Y7") (pinfunction "IO_L23N_T3_34_Y7") (pintype "bidirectional"))
    )
    (net (code "24") (name "/DDR3_CKE") (class "Default")
      (node (ref "U10F") (pin "Y8") (pinfunction "IO_L23P_T3_34_Y8") (pintype "bidirectional"))
    )
    (net (code "25") (name "/DDR3_CK_N") (class "Default")
      (node (ref "U10F") (pin "R2") (pinfunction "IO_L3N_T0_DQS_34_R2") (pintype "bidirectional"))
    )
    (net (code "26") (name "/DDR3_CK_P") (class "Default")
      (node (ref "U10F") (pin "R3") (pinfunction "IO_L3P_T0_DQS_34_R3") (pintype "bidirectional"))
    )
    (net (code "27") (name "/DDR3_CS0_N") (class "Default")
      (node (ref "U10F") (pin "V9") (pinfunction "IO_L21P_T3_DQS_34_V9") (pintype "bidirectional"))
    )
    (net (code "28") (name "/DDR3_DM0") (class "Default")
      (node (ref "U10F") (pin "G1") (pinfunction "IO_L5P_T0_AD13P_35_G1") (pintype "bidirectional"))
    )
    (net (code "29") (name "/DDR3_DM1") (class "Default")
      (node (ref "U10F") (pin "H4") (pinfunction "IO_L12P_T1_MRCC_35_H4") (pintype "bidirectional"))
    )
    (net (code "30") (name "/DDR3_DM2") (class "Default")
      (node (ref "U10F") (pin "M5") (pinfunction "IO_L23N_T3_35_M5") (pintype "bidirectional"))
    )
    (net (code "31") (name "/DDR3_DM3") (class "Default")
      (node (ref "U10F") (pin "L3") (pinfunction "IO_L14P_T2_SRCC_35_L3") (pintype "bidirectional"))
    )
    (net (code "32") (name "/DDR3_DQ0") (class "Default")
      (node (ref "U10F") (pin "C2") (pinfunction "IO_L2P_T0_AD12P_35_C2") (pintype "bidirectional"))
    )
    (net (code "33") (name "/DDR3_DQ1") (class "Default")
      (node (ref "U10F") (pin "F1") (pinfunction "IO_L5N_T0_AD13N_35_F1") (pintype "bidirectional"))
    )
    (net (code "34") (name "/DDR3_DQ2") (class "Default")
      (node (ref "U10F") (pin "B1") (pinfunction "IO_L1P_T0_AD4P_35_B1") (pintype "bidirectional"))
    )
    (net (code "35") (name "/DDR3_DQ3") (class "Default")
      (node (ref "U10F") (pin "F3") (pinfunction "IO_L6P_T0_35_F3") (pintype "bidirectional"))
    )
    (net (code "36") (name "/DDR3_DQ4") (class "Default")
      (node (ref "U10F") (pin "A1") (pinfunction "IO_L1N_T0_AD4N_35_A1") (pintype "bidirectional"))
    )
    (net (code "37") (name "/DDR3_DQ5") (class "Default")
      (node (ref "U10F") (pin "D2") (pinfunction "IO_L4N_T0_35_D2") (pintype "bidirectional"))
    )
    (net (code "38") (name "/DDR3_DQ6") (class "Default")
      (node (ref "U10F") (pin "B2") (pinfunction "IO_L2N_T0_AD12N_35_B2") (pintype "bidirectional"))
    )
    (net (code "39") (name "/DDR3_DQ7") (class "Default")
      (node (ref "U10F") (pin "E2") (pinfunction "IO_L4P_T0_35_E2") (pintype "bidirectional"))
    )
    (net (code "40") (name "/DDR3_DQ8") (class "Default")
      (node (ref "U10F") (pin "J5") (pinfunction "IO_L10P_T1_AD15P_35_J5") (pintype "bidirectional"))
    )
    (net (code "41") (name "/DDR3_DQ9") (class "Default")
      (node (ref "U10F") (pin "H3") (pinfunction "IO_L11P_T1_SRCC_35_H3") (pintype "bidirectional"))
    )
    (net (code "42") (name "/DDR3_DQ10") (class "Default")
      (node (ref "U10F") (pin "K1") (pinfunction "IO_L7P_T1_AD6P_35_K1") (pintype "bidirectional"))
    )
    (net (code "43") (name "/DDR3_DQ11") (class "Default")
      (node (ref "U10F") (pin "H2") (pinfunction "IO_L8P_T1_AD14P_35_H2") (pintype "bidirectional"))
    )
    (net (code "44") (name "/DDR3_DQ12") (class "Default")
      (node (ref "U10F") (pin "J1") (pinfunction "IO_L7N_T1_AD6N_35_J1") (pintype "bidirectional"))
    )
    (net (code "45") (name "/DDR3_DQ13") (class "Default")
      (node (ref "U10F") (pin "G2") (pinfunction "IO_L8N_T1_AD14N_35_G2") (pintype "bidirectional"))
    )
    (net (code "46") (name "/DDR3_DQ14") (class "Default")
      (node (ref "U10F") (pin "H5") (pinfunction "IO_L10N_T1_AD15N_35_H5") (pintype "bidirectional"))
    )
    (net (code "47") (name "/DDR3_DQ15") (class "Default")
      (node (ref "U10F") (pin "G3") (pinfunction "IO_L11N_T1_SRCC_35_G3") (pintype "bidirectional"))
    )
    (net (code "48") (name "/DDR3_DQ16") (class "Default")
      (node (ref "U10F") (pin "N2") (pinfunction "IO_L22N_T3_35_N2") (pintype "bidirectional"))
    )
    (net (code "49") (name "/DDR3_DQ17") (class "Default")
      (node (ref "U10F") (pin "M6") (pinfunction "IO_L23P_T3_35_M6") (pintype "bidirectional"))
    )
    (net (code "50") (name "/DDR3_DQ18") (class "Default")
      (node (ref "U10F") (pin "P1") (pinfunction "IO_L20N_T3_35_P1") (pintype "bidirectional"))
    )
    (net (code "51") (name "/DDR3_DQ19") (class "Default")
      (node (ref "U10F") (pin "N5") (pinfunction "IO_L24N_T3_35_N5") (pintype "bidirectional"))
    )
    (net (code "52") (name "/DDR3_DQ20") (class "Default")
      (node (ref "U10F") (pin "P2") (pinfunction "IO_L22P_T3_35_P2") (pintype "bidirectional"))
    )
    (net (code "53") (name "/DDR3_DQ21") (class "Default")
      (node (ref "U10F") (pin "N4") (pinfunction "IO_L19P_T3_35_N4") (pintype "bidirectional"))
    )
    (net (code "54") (name "/DDR3_DQ22") (class "Default")
      (node (ref "U10F") (pin "R1") (pinfunction "IO_L20P_T3_35_R1") (pintype "bidirectional"))
    )
    (net (code "55") (name "/DDR3_DQ23") (class "Default")
      (node (ref "U10F") (pin "P6") (pinfunction "IO_L24P_T3_35_P6") (pintype "bidirectional"))
    )
    (net (code "56") (name "/DDR3_DQ24") (class "Default")
      (node (ref "U10F") (pin "K3") (pinfunction "IO_L14N_T2_SRCC_35_K3") (pintype "bidirectional"))
    )
    (net (code "57") (name "/DDR3_DQ25") (class "Default")
      (node (ref "U10F") (pin "M2") (pinfunction "IO_L16N_T2_35_M2") (pintype "bidirectional"))
    )
    (net (code "58") (name "/DDR3_DQ26") (class "Default")
      (node (ref "U10F") (pin "K4") (pinfunction "IO_L13P_T2_MRCC_35_K4") (pintype "bidirectional"))
    )
    (net (code "59") (name "/DDR3_DQ27") (class "Default")
      (node (ref "U10F") (pin "M3") (pinfunction "IO_L16P_T2_35_M3") (pintype "bidirectional"))
    )
    (net (code "60") (name "/DDR3_DQ28") (class "Default")
      (node (ref "U10F") (pin "J6") (pinfunction "IO_L17N_T2_35_J6") (pintype "bidirectional"))
    )
    (net (code "61") (name "/DDR3_DQ29") (class "Default")
      (node (ref "U10F") (pin "L5") (pinfunction "IO_L18P_T2_35_L5") (pintype "bidirectional"))
    )
    (net (code "62") (name "/DDR3_DQ30") (class "Default")
      (node (ref "U10F") (pin "J4") (pinfunction "IO_L13N_T2_MRCC_35_J4") (pintype "bidirectional"))
    )
    (net (code "63") (name "/DDR3_DQ31") (class "Default")
      (node (ref "U10F") (pin "K6") (pinfunction "IO_L17P_T2_35_K6") (pintype "bidirectional"))
    )
    (net (code "64") (name "/DDR3_DQS0_N") (class "Default")
      (node (ref "U10F") (pin "D1") (pinfunction "IO_L3N_T0_DQS_AD5N_35_D1") (pintype "bidirectional"))
    )
    (net (code "65") (name "/DDR3_DQS0_P") (class "Default")
      (node (ref "U10F") (pin "E1") (pinfunction "IO_L3P_T0_DQS_AD5P_35_E1") (pintype "bidirectional"))
    )
    (net (code "66") (name "/DDR3_DQS1_N") (class "Default")
      (node (ref "U10F") (pin "J2") (pinfunction "IO_L9N_T1_DQS_AD7N_35_J2") (pintype "bidirectional"))
    )
    (net (code "67") (name "/DDR3_DQS1_P") (class "Default")
      (node (ref "U10F") (pin "K2") (pinfunction "IO_L9P_T1_DQS_AD7P_35_K2") (pintype "bidirectional"))
    )
    (net (code "68") (name "/DDR3_DQS2_N") (class "Default")
      (node (ref "U10F") (pin "P4") (pinfunction "IO_L21N_T3_DQS_35_P4") (pintype "bidirectional"))
    )
    (net (code "69") (name "/DDR3_DQS2_P") (class "Default")
      (node (ref "U10F") (pin "P5") (pinfunction "IO_L21P_T3_DQS_35_P5") (pintype "bidirectional"))
    )
    (net (code "70") (name "/DDR3_DQS3_N") (class "Default")
      (node (ref "U10F") (pin "L1") (pinfunction "IO_L15N_T2_DQS_35_L1") (pintype "bidirectional"))
    )
    (net (code "71") (name "/DDR3_DQS3_P") (class "Default")
      (node (ref "U10F") (pin "M1") (pinfunction "IO_L15P_T2_DQS_35_M1") (pintype "bidirectional"))
    )
    (net (code "72") (name "/DDR3_ODT0") (class "Default")
      (node (ref "U10F") (pin "W9") (pinfunction "IO_L24P_T3_34_W9") (pintype "bidirectional"))
    )
    (net (code "73") (name "/DDR3_RAS_N") (class "Default")
      (node (ref "U10F") (pin "Y9") (pinfunction "IO_L24N_T3_34_Y9") (pintype "bidirectional"))
    )
    (net (code "74") (name "/DDR3_RESET_N") (class "Default")
      (node (ref "U10F") (pin "AB5") (pinfunction "IO_L10N_T1_34_AB5") (pintype "bidirectional"))
    )
    (net (code "75") (name "/DDR3_WE_N") (class "Default")
      (node (ref "U10F") (pin "V8") (pinfunction "IO_L21N_T3_DQS_34_V8") (pintype "bidirectional"))
    )
    (net (code "76") (name "/ETH_50MHZ") (class "Default")
      (node (ref "U10F") (pin "D17") (pinfunction "IO_L12P_T1_MRCC_16_D17") (pintype "bidirectional"))
    )
    (net (code "77") (name "/ETH_CRS_DV") (class "Default")
      (node (ref "U10F") (pin "C20") (pinfunction "IO_L19N_T3_VREF_16_C20") (pintype "bidirectional"))
    )
    (net (code "78") (name "/ETH_INTRP") (class "Default")
      (node (ref "U10F") (pin "D21") (pinfunction "IO_L23N_T3_16_D21") (pintype "bidirectional"))
    )
    (net (code "79") (name "/ETH_MDC") (class "Default")
      (node (ref "U10F") (pin "F14") (pinfunction "IO_L1N_T0_16_F14") (pintype "bidirectional"))
    )
    (net (code "80") (name "/ETH_MDIO") (class "Default")
      (node (ref "U10F") (pin "F13") (pinfunction "IO_L1P_T0_16_F13") (pintype "bidirectional"))
    )
    (net (code "81") (name "/ETH_RST") (class "Default")
      (node (ref "U10F") (pin "F16") (pinfunction "IO_L2P_T0_16_F16") (pintype "bidirectional"))
    )
    (net (code "82") (name "/ETH_RXD0") (class "Default")
      (node (ref "U10F") (pin "A20") (pinfunction "IO_L16N_T2_16_A20") (pintype "bidirectional"))
    )
    (net (code "83") (name "/ETH_RXD1") (class "Default")
      (node (ref "U10F") (pin "B18") (pinfunction "IO_L11N_T1_SRCC_16_B18") (pintype "bidirectional"))
    )
    (net (code "84") (name "/ETH_RXER") (class "Default")
      (node (ref "U10F") (pin "B20") (pinfunction "IO_L16P_T2_16_B20") (pintype "bidirectional"))
    )
    (net (code "85") (name "/ETH_TXD0") (class "Default")
      (node (ref "U10F") (pin "C18") (pinfunction "IO_L13P_T2_MRCC_16_C18") (pintype "bidirectional"))
    )
    (net (code "86") (name "/ETH_TXD1") (class "Default")
      (node (ref "U10F") (pin "C19") (pinfunction "IO_L13N_T2_MRCC_16_C19") (pintype "bidirectional"))
    )
    (net (code "87") (name "/ETH_TXEN") (class "Default")
      (node (ref "U10F") (pin "A19") (pinfunction "IO_L17N_T2_16_A19") (pintype "bidirectional"))
    )
    (net (code "88") (name "/FAN_PWM") (class "Default")
      (node (ref "U10F") (pin "L14") (pinfunction "IO_L22P_T3_A17_15_L14") (pintype "bidirectional"))
    )
    (net (code "89") (name "/FPGA_DONE") (class "Default")
      (node (ref "R14F") (pin "1") (pinfunction "1_1") (pintype "passive"))
      (node (ref "U10F") (pin "G11") (pinfunction "DONE_0_G11") (pintype "bidirectional"))
    )
    (net (code "90") (name "/FPGA_INIT") (class "Default")
      (node (ref "R13F") (pin "1") (pinfunction "1_1") (pintype "passive"))
      (node (ref "U10F") (pin "U12") (pinfunction "INIT_B_0_U12") (pintype "bidirectional"))
    )
    (net (code "91") (name "/FPGA_LED0") (class "Default")
      (node (ref "U10F") (pin "M21") (pinfunction "IO_L10P_T1_AD11P_15_M21") (pintype "bidirectional"))
    )
    (net (code "92") (name "/FPGA_LED1") (class "Default")
      (node (ref "U10F") (pin "N20") (pinfunction "IO_L18P_T2_A24_15_N20") (pintype "bidirectional"))
    )
    (net (code "93") (name "/FPGA_LED2") (class "Default")
      (node (ref "U10F") (pin "L21") (pinfunction "IO_L10N_T1_AD11N_15_L21") (pintype "bidirectional"))
    )
    (net (code "94") (name "/FPGA_LED3") (class "Default")
      (node (ref "U10F") (pin "AA21") (pinfunction "IO_L8N_T1_D12_14_AA21") (pintype "bidirectional"))
    )
    (net (code "95") (name "/FPGA_LED4") (class "Default")
      (node (ref "U10F") (pin "R19") (pinfunction "IO_L5N_T0_D07_14_R19") (pintype "bidirectional"))
    )
    (net (code "96") (name "/FPGA_LED5") (class "Default")
      (node (ref "U10F") (pin "M16") (pinfunction "IO_L24N_T3_RS0_15_M16") (pintype "bidirectional"))
    )
    (net (code "97") (name "/FPGA_MODE") (class "Default")
      (node (ref "P10F") (pin "1") (pinfunction "1_1") (pintype "passive"))
      (node (ref "R15F") (pin "2") (pinfunction "2_2") (pintype "passive"))
      (node (ref "U10F") (pin "U9") (pinfunction "M2_0_U9") (pintype "input"))
    )
    (net (code "98") (name "/FPGA_PROGRAM_B") (class "Default")
      (node (ref "R12F") (pin "1") (pinfunction "1_1") (pintype "passive"))
      (node (ref "U10F") (pin "N12") (pinfunction "PROGRAM_B_0_N12") (pintype "input"))
    )
    (net (code "99") (name "/FPGA_PUDC") (class "Default")
      (node (ref "R10F") (pin "1") (pinfunction "1_1") (pintype "passive"))
      (node (ref "U10F") (pin "U22") (pinfunction "IO_L3P_T0_DQS_PUDC_B_14_U22") (pintype "bidirectional"))
    )
    (net (code "100") (name "/FPGA_SPI_CS") (class "Default")
      (node (ref "U10F") (pin "T19") (pinfunction "IO_L6P_T0_FCS_B_14_T19") (pintype "bidirectional"))
    )
    (net (code "101") (name "/FPGA_SPI_MISO_D1") (class "Default")
      (node (ref "U10F") (pin "R22") (pinfunction "IO_L1N_T0_D01_DIN_14_R22") (pintype "bidirectional"))
    )
    (net (code "102") (name "/FPGA_SPI_MOSI_D0") (class "Default")
      (node (ref "U10F") (pin "P22") (pinfunction "IO_L1P_T0_D00_MOSI_14_P22") (pintype "bidirectional"))
    )
    (net (code "103") (name "/FPGA_SPI_RES_D3") (class "Default")
      (node (ref "U10F") (pin "R21") (pinfunction "IO_L2N_T0_D03_14_R21") (pintype "bidirectional"))
    )
    (net (code "104") (name "/FPGA_SPI_SCK") (class "Default")
      (node (ref "U10F") (pin "L12") (pinfunction "CCLK_0_L12") (pintype "bidirectional"))
    )
    (net (code "105") (name "/FPGA_SPI_WP_D2") (class "Default")
      (node (ref "U10F") (pin "P21") (pinfunction "IO_L2P_T0_D02_14_P21") (pintype "bidirectional"))
    )
    (net (code "106") (name "/FPGA_TCK") (class "Default")
      (node (ref "U10F") (pin "V12") (pinfunction "TCK_0_V12") (pintype "input"))
    )
    (net (code "107") (name "/FPGA_TDI") (class "Default")
      (node (ref "U10F") (pin "R13") (pinfunction "TDI_0_R13") (pintype "input"))
    )
    (net (code "108") (name "/FPGA_TDO") (class "Default")
      (node (ref "U10F") (pin "U13") (pinfunction "TDO_0_U13") (pintype "output"))
    )
    (net (code "109") (name "/FPGA_TMS") (class "Default")
      (node (ref "U10F") (pin "T13") (pinfunction "TMS_0_T13") (pintype "input"))
    )
    (net (code "110") (name "/FUSB_N") (class "Default")
      (node (ref "U10F") (pin "C15") (pinfunction "IO_L3N_T0_DQS_16_C15") (pintype "bidirectional"))
    )
    (net (code "111") (name "/FUSB_P") (class "Default")
      (node (ref "U10F") (pin "C14") (pinfunction "IO_L3P_T0_DQS_16_C14") (pintype "bidirectional"))
    )
    (net (code "112") (name "/HAX_0") (class "Default")
      (node (ref "U10F") (pin "B15") (pinfunction "IO_L7P_T1_16_B15") (pintype "bidirectional"))
    )
    (net (code "113") (name "/HAX_1") (class "Default")
      (node (ref "U10F") (pin "B16") (pinfunction "IO_L7N_T1_16_B16") (pintype "bidirectional"))
    )
    (net (code "114") (name "/HAX_2") (class "Default")
      (node (ref "U10F") (pin "B13") (pinfunction "IO_L8N_T1_16_B13") (pintype "bidirectional"))
    )
    (net (code "115") (name "/HAX_3") (class "Default")
      (node (ref "U10F") (pin "A15") (pinfunction "IO_L9P_T1_DQS_16_A15") (pintype "bidirectional"))
    )
    (net (code "116") (name "/HAX_4") (class "Default")
      (node (ref "U10F") (pin "A16") (pinfunction "IO_L9N_T1_DQS_16_A16") (pintype "bidirectional"))
    )
    (net (code "117") (name "/HAX_5") (class "Default")
      (node (ref "U10F") (pin "A13") (pinfunction "IO_L10P_T1_16_A13") (pintype "bidirectional"))
    )
    (net (code "118") (name "/HAX_6") (class "Default")
      (node (ref "U10F") (pin "A14") (pinfunction "IO_L10N_T1_16_A14") (pintype "bidirectional"))
    )
    (net (code "119") (name "/HAX_7") (class "Default")
      (node (ref "U10F") (pin "B17") (pinfunction "IO_L11P_T1_SRCC_16_B17") (pintype "bidirectional"))
    )
    (net (code "120") (name "/HAX_8") (class "Default")
      (node (ref "U10F") (pin "A18") (pinfunction "IO_L17P_T2_16_A18") (pintype "bidirectional"))
    )
    (net (code "121") (name "/HAX_9") (class "Default")
      (node (ref "U10F") (pin "C17") (pinfunction "IO_L12N_T1_MRCC_16_C17") (pintype "bidirectional"))
    )
    (net (code "122") (name "/HAX_CLK_N") (class "Default")
      (node (ref "U10F") (pin "E6") (pinfunction "MGTREFCLK0N_216_E6") (pintype "input"))
    )
    (net (code "123") (name "/HAX_CLK_P") (class "Default")
      (node (ref "U10F") (pin "F6") (pinfunction "MGTREFCLK0P_216_F6") (pintype "input"))
    )
    (net (code "124") (name "/HDMI_HPD_LL_N") (class "Default")
      (node (ref "U10F") (pin "U17") (pinfunction "IO_L18P_T2_A12_D28_14_U17") (pintype "bidirectional"))
    )
    (net (code "125") (name "/MCU_INT0") (class "Default")
      (node (ref "U10F") (pin "D15") (pinfunction "IO_L6N_T0_VREF_16_D15") (pintype "bidirectional"))
    )
    (net (code "126") (name "/MCU_INT1") (class "Default")
      (node (ref "U10F") (pin "G13") (pinfunction "IO_L1N_T0_AD0N_15_G13") (pintype "bidirectional"))
    )
    (net (code "127") (name "/OV0_CEC_R") (class "Default")
      (node (ref "U10F") (pin "P19") (pinfunction "IO_L5P_T0_D06_14_P19") (pintype "bidirectional"))
    )
    (net (code "128") (name "/OV0_DDC_SCL_LV") (class "Default")
      (node (ref "U10F") (pin "W17") (pinfunction "IO_L16N_T2_A15_D31_14_W17") (pintype "bidirectional"))
    )
    (net (code "129") (name "/OV0_DDC_SDA_LV") (class "Default")
      (node (ref "U10F") (pin "R17") (pinfunction "IO_L24N_T3_A00_D16_14_R17") (pintype "bidirectional"))
    )
    (net (code "130") (name "/OV0_HDMI_HPD_LV") (class "Default")
      (node (ref "U10F") (pin "V17") (pinfunction "IO_L16P_T2_CSI_B_14_V17") (pintype "bidirectional"))
    )
    (net (code "131") (name "/OV0_TMDS0_N") (class "Default")
      (node (ref "U10F") (pin "AB18") (pinfunction "IO_L17N_T2_A13_D29_14_AB18") (pintype "bidirectional"))
    )
    (net (code "132") (name "/OV0_TMDS0_P") (class "Default")
      (node (ref "U10F") (pin "AA18") (pinfunction "IO_L17P_T2_A14_D30_14_AA18") (pintype "bidirectional"))
    )
    (net (code "133") (name "/OV0_TMDS1_N") (class "Default")
      (node (ref "U10F") (pin "AA19") (pinfunction "IO_L15P_T2_DQS_RDWR_B_14_AA19") (pintype "bidirectional"))
    )
    (net (code "134") (name "/OV0_TMDS1_P") (class "Default")
      (node (ref "U10F") (pin "AB20") (pinfunction "IO_L15N_T2_DQS_DOUT_CSO_B_14_AB20") (pintype "bidirectional"))
    )
    (net (code "135") (name "/OV0_TMDS2_N") (class "Default")
      (node (ref "U10F") (pin "AB21") (pinfunction "IO_L10P_T1_D14_14_AB21") (pintype "bidirectional"))
    )
    (net (code "136") (name "/OV0_TMDS2_P") (class "Default")
      (node (ref "U10F") (pin "AB22") (pinfunction "IO_L10N_T1_D15_14_AB22") (pintype "bidirectional"))
    )
    (net (code "137") (name "/OV0_TMDS3_N") (class "Default")
      (node (ref "U10F") (pin "Y18") (pinfunction "IO_L13P_T2_MRCC_14_Y18") (pintype "bidirectional"))
    )
    (net (code "138") (name "/OV0_TMDS3_P") (class "Default")
      (node (ref "U10F") (pin "Y19") (pinfunction "IO_L13N_T2_MRCC_14_Y19") (pintype "bidirectional"))
    )
    (net (code "139") (name "/PCICLK_N") (class "Default")
      (node (ref "C23F") (pin "1") (pinfunction "1_1") (pintype "passive"))
      (node (ref "U10F") (pin "E10") (pinfunction "MGTREFCLK1N_216_E10") (pintype "input"))
    )
    (net (code "140") (name "/PCICLK_P") (class "Default")
      (node (ref "C21F") (pin "1") (pinfunction "1_1") (pintype "passive"))
      (node (ref "U10F") (pin "F10") (pinfunction "MGTREFCLK1P_216_F10") (pintype "input"))
    )
    (net (code "141") (name "/PER0_N") (class "Default")
      (node (ref "C25F") (pin "1") (pinfunction "1_1") (pintype "passive"))
    )
    (net (code "142") (name "/PER0_P") (class "Default")
      (node (ref "C24F") (pin "1") (pinfunction "1_1") (pintype "passive"))
    )
    (net (code "143") (name "/PER1_N") (class "Default")
      (node (ref "C36F") (pin "1") (pinfunction "1_1") (pintype "passive"))
    )
    (net (code "144") (name "/PER1_P") (class "Default")
      (node (ref "C27F") (pin "1") (pinfunction "1_1") (pintype "passive"))
    )
    (net (code "145") (name "/PER2_N") (class "Default")
      (node (ref "C40F") (pin "1") (pinfunction "1_1") (pintype "passive"))
    )
    (net (code "146") (name "/PER2_P") (class "Default")
      (node (ref "C37F") (pin "1") (pinfunction "1_1") (pintype "passive"))
    )
    (net (code "147") (name "/PER3_N") (class "Default")
      (node (ref "C22F") (pin "1") (pinfunction "1_1") (pintype "passive"))
    )
    (net (code "148") (name "/PER3_P") (class "Default")
      (node (ref "C20F") (pin "1") (pinfunction "1_1") (pintype "passive"))
    )
    (net (code "149") (name "/PERC0_N") (class "Default")
      (node (ref "C25F") (pin "2") (pinfunction "2_2") (pintype "passive"))
      (node (ref "U10F") (pin "C5") (pinfunction "MGTPTXN1_216_C5") (pintype "output"))
    )
    (net (code "150") (name "/PERC0_P") (class "Default")
      (node (ref "C24F") (pin "2") (pinfunction "2_2") (pintype "passive"))
      (node (ref "U10F") (pin "D5") (pinfunction "MGTPTXP1_216_D5") (pintype "output"))
    )
    (net (code "151") (name "/PERC1_N") (class "Default")
      (node (ref "C36F") (pin "2") (pinfunction "2_2") (pintype "passive"))
      (node (ref "U10F") (pin "A6") (pinfunction "MGTPTXN2_216_A6") (pintype "output"))
    )
    (net (code "152") (name "/PERC1_P") (class "Default")
      (node (ref "C27F") (pin "2") (pinfunction "2_2") (pintype "passive"))
      (node (ref "U10F") (pin "B6") (pinfunction "MGTPTXP2_216_B6") (pintype "output"))
    )
    (net (code "153") (name "/PERC2_N") (class "Default")
      (node (ref "C40F") (pin "2") (pinfunction "2_2") (pintype "passive"))
      (node (ref "U10F") (pin "C7") (pinfunction "MGTPTXN3_216_C7") (pintype "output"))
    )
    (net (code "154") (name "/PERC2_P") (class "Default")
      (node (ref "C37F") (pin "2") (pinfunction "2_2") (pintype "passive"))
      (node (ref "U10F") (pin "D7") (pinfunction "MGTPTXP3_216_D7") (pintype "output"))
    )
    (net (code "155") (name "/PERC3_N") (class "Default")
      (node (ref "C22F") (pin "2") (pinfunction "2_2") (pintype "passive"))
      (node (ref "U10F") (pin "A4") (pinfunction "MGTPTXN0_216_A4") (pintype "output"))
    )
    (net (code "156") (name "/PERC3_P") (class "Default")
      (node (ref "C20F") (pin "2") (pinfunction "2_2") (pintype "passive"))
      (node (ref "U10F") (pin "B4") (pinfunction "MGTPTXP0_216_B4") (pintype "output"))
    )
    (net (code "157") (name "/PERST#") (class "Default")
      (node (ref "U10F") (pin "E18") (pinfunction "IO_L15N_T2_DQS_16_E18") (pintype "bidirectional"))
    )
    (net (code "158") (name "/PET0_N") (class "Default")
      (node (ref "U10F") (pin "C11") (pinfunction "MGTPRXN1_216_C11") (pintype "input"))
    )
    (net (code "159") (name "/PET0_P") (class "Default")
      (node (ref "U10F") (pin "D11") (pinfunction "MGTPRXP1_216_D11") (pintype "input"))
    )
    (net (code "160") (name "/PET1_N") (class "Default")
      (node (ref "U10F") (pin "A10") (pinfunction "MGTPRXN2_216_A10") (pintype "input"))
    )
    (net (code "161") (name "/PET1_P") (class "Default")
      (node (ref "U10F") (pin "B10") (pinfunction "MGTPRXP2_216_B10") (pintype "input"))
    )
    (net (code "162") (name "/PET2_N") (class "Default")
      (node (ref "U10F") (pin "C9") (pinfunction "MGTPRXN3_216_C9") (pintype "input"))
    )
    (net (code "163") (name "/PET2_P") (class "Default")
      (node (ref "U10F") (pin "D9") (pinfunction "MGTPRXP3_216_D9") (pintype "input"))
    )
    (net (code "164") (name "/PET3_N") (class "Default")
      (node (ref "U10F") (pin "A8") (pinfunction "MGTPRXN0_216_A8") (pintype "input"))
    )
    (net (code "165") (name "/PET3_P") (class "Default")
      (node (ref "U10F") (pin "B8") (pinfunction "MGTPRXP0_216_B8") (pintype "input"))
    )
    (net (code "166") (name "/REFCLK_N") (class "Default")
      (node (ref "C23F") (pin "2") (pinfunction "2_2") (pintype "passive"))
    )
    (net (code "167") (name "/REFCLK_P") (class "Default")
      (node (ref "C21F") (pin "2") (pinfunction "2_2") (pintype "passive"))
    )
    (net (code "168") (name "/RX0_FORCEPLUG") (class "Default")
      (node (ref "U10F") (pin "N22") (pinfunction "IO_L15P_T2_DQS_15_N22") (pintype "bidirectional"))
    )
    (net (code "169") (name "/RX0_FORCEUNPLUG") (class "Default")
      (node (ref "U10F") (pin "M22") (pinfunction "IO_L15N_T2_DQS_ADV_B_15_M22") (pintype "bidirectional"))
    )
    (net (code "170") (name "/RX0_TMDS0_N") (class "Default")
      (node (ref "U10F") (pin "K21") (pinfunction "IO_L9P_T1_DQS_AD3P_15_K21") (pintype "bidirectional"))
    )
    (net (code "171") (name "/RX0_TMDS0_P") (class "Default")
      (node (ref "U10F") (pin "K22") (pinfunction "IO_L9N_T1_DQS_AD3N_15_K22") (pintype "bidirectional"))
    )
    (net (code "172") (name "/RX0_TMDS1_N") (class "Default")
      (node (ref "U10F") (pin "J20") (pinfunction "IO_L11P_T1_SRCC_15_J20") (pintype "bidirectional"))
    )
    (net (code "173") (name "/RX0_TMDS1_P") (class "Default")
      (node (ref "U10F") (pin "J21") (pinfunction "IO_L11N_T1_SRCC_15_J21") (pintype "bidirectional"))
    )
    (net (code "174") (name "/RX0_TMDS2_N") (class "Default")
      (node (ref "U10F") (pin "J22") (pinfunction "IO_L7P_T1_AD2P_15_J22") (pintype "bidirectional"))
    )
    (net (code "175") (name "/RX0_TMDS2_P") (class "Default")
      (node (ref "U10F") (pin "H22") (pinfunction "IO_L7N_T1_AD2N_15_H22") (pintype "bidirectional"))
    )
    (net (code "176") (name "/RX0_TMDS3_N") (class "Default")
      (node (ref "U10F") (pin "L19") (pinfunction "IO_L14P_T2_SRCC_15_L19") (pintype "bidirectional"))
    )
    (net (code "177") (name "/RX0_TMDS3_P") (class "Default")
      (node (ref "U10F") (pin "L20") (pinfunction "IO_L14N_T2_SRCC_15_L20") (pintype "bidirectional"))
    )
    (net (code "178") (name "/SD_CLK") (class "Default")
      (node (ref "U10F") (pin "K18") (pinfunction "IO_L13P_T2_MRCC_15_K18") (pintype "bidirectional"))
    )
    (net (code "179") (name "/SD_CMD") (class "Default")
      (node (ref "U10F") (pin "L13") (pinfunction "IO_L20N_T3_A19_15_L13") (pintype "bidirectional"))
    )
    (net (code "180") (name "/SD_DAT0") (class "Default")
      (node (ref "U10F") (pin "L15") (pinfunction "IO_L22N_T3_A16_15_L15") (pintype "bidirectional"))
    )
    (net (code "181") (name "/SD_DAT1") (class "Default")
      (node (ref "U10F") (pin "L16") (pinfunction "IO_L23P_T3_FOE_B_15_L16") (pintype "bidirectional"))
    )
    (net (code "182") (name "/SD_DAT2") (class "Default")
      (node (ref "U10F") (pin "K14") (pinfunction "IO_L19N_T3_A21_VREF_15_K14") (pintype "bidirectional"))
    )
    (net (code "183") (name "/SD_DAT3") (class "Default")
      (node (ref "U10F") (pin "M13") (pinfunction "IO_L20P_T3_A20_15_M13") (pintype "bidirectional"))
    )
    (net (code "184") (name "/SM_N") (class "Default")
      (node (ref "U10F") (pin "D19") (pinfunction "IO_L14N_T2_SRCC_16_D19") (pintype "bidirectional"))
    )
    (net (code "185") (name "/SM_P") (class "Default")
      (node (ref "U10F") (pin "E19") (pinfunction "IO_L14P_T2_SRCC_16_E19") (pintype "bidirectional"))
    )
    (net (code "186") (name "/SYSCLK") (class "Default")
      (node (ref "U10F") (pin "J19") (pinfunction "IO_L12P_T1_MRCC_15_J19") (pintype "bidirectional"))
      (node (ref "U11F") (pin "3") (pinfunction "OUT_3") (pintype "output"))
    )
    (net (code "187") (name "/TX0_SCL_LV") (class "Default")
      (node (ref "U10F") (pin "F21") (pinfunction "IO_25_16_F21") (pintype "bidirectional"))
    )
    (net (code "188") (name "/TX0_SDA_LV") (class "Default")
      (node (ref "U10F") (pin "H18") (pinfunction "IO_L6N_T0_VREF_15_H18") (pintype "bidirectional"))
    )
    (net (code "189") (name "/TX0_TMDS0_N") (class "Default")
      (node (ref "U10F") (pin "W22") (pinfunction "IO_L7N_T1_D10_14_W22") (pintype "bidirectional"))
    )
    (net (code "190") (name "/TX0_TMDS0_P") (class "Default")
      (node (ref "U10F") (pin "W21") (pinfunction "IO_L7P_T1_D09_14_W21") (pintype "bidirectional"))
    )
    (net (code "191") (name "/TX0_TMDS1_N") (class "Default")
      (node (ref "U10F") (pin "V20") (pinfunction "IO_L11N_T1_SRCC_14_V20") (pintype "bidirectional"))
    )
    (net (code "192") (name "/TX0_TMDS1_P") (class "Default")
      (node (ref "U10F") (pin "U20") (pinfunction "IO_L11P_T1_SRCC_14_U20") (pintype "bidirectional"))
    )
    (net (code "193") (name "/TX0_TMDS2_N") (class "Default")
      (node (ref "U10F") (pin "U21") (pinfunction "IO_L4N_T0_D05_14_U21") (pintype "bidirectional"))
    )
    (net (code "194") (name "/TX0_TMDS2_P") (class "Default")
      (node (ref "U10F") (pin "T21") (pinfunction "IO_L4P_T0_D04_14_T21") (pintype "bidirectional"))
    )
    (net (code "195") (name "/TX0_TMDS3_N") (class "Default")
      (node (ref "U10F") (pin "W19") (pinfunction "IO_L12P_T1_MRCC_14_W19") (pintype "bidirectional"))
    )
    (net (code "196") (name "/TX0_TMDS3_P") (class "Default")
      (node (ref "U10F") (pin "W20") (pinfunction "IO_L12N_T1_MRCC_14_W20") (pintype "bidirectional"))
    )
    (net (code "197") (name "/TX1_CEC") (class "Default")
      (node (ref "U10F") (pin "P17") (pinfunction "IO_L21N_T3_DQS_A06_D22_14_P17") (pintype "bidirectional"))
    )
    (net (code "198") (name "/TX1_CLK_N") (class "Default")
      (node (ref "U10F") (pin "G21") (pinfunction "IO_L24P_T3_16_G21") (pintype "bidirectional"))
    )
    (net (code "199") (name "/TX1_CLK_P") (class "Default")
      (node (ref "U10F") (pin "G22") (pinfunction "IO_L24N_T3_16_G22") (pintype "bidirectional"))
    )
    (net (code "200") (name "/TX1_HPD_LL") (class "Default")
      (node (ref "U10F") (pin "U18") (pinfunction "IO_L18N_T2_A11_D27_14_U18") (pintype "bidirectional"))
    )
    (net (code "201") (name "/TX1_SCL_LV") (class "Default")
      (node (ref "U10F") (pin "P16") (pinfunction "IO_L24P_T3_A01_D17_14_P16") (pintype "bidirectional"))
    )
    (net (code "202") (name "/TX1_SDA_LV") (class "Default")
      (node (ref "U10F") (pin "R16") (pinfunction "IO_L22N_T3_A04_D20_14_R16") (pintype "bidirectional"))
    )
    (net (code "203") (name "/TX1_TMDS0_N") (class "Default")
      (node (ref "U10F") (pin "E22") (pinfunction "IO_L22P_T3_16_E22") (pintype "bidirectional"))
    )
    (net (code "204") (name "/TX1_TMDS0_P") (class "Default")
      (node (ref "U10F") (pin "D22") (pinfunction "IO_L22N_T3_16_D22") (pintype "bidirectional"))
    )
    (net (code "205") (name "/TX1_TMDS1_N") (class "Default")
      (node (ref "U10F") (pin "C22") (pinfunction "IO_L20P_T3_16_C22") (pintype "bidirectional"))
    )
    (net (code "206") (name "/TX1_TMDS1_P") (class "Default")
      (node (ref "U10F") (pin "B22") (pinfunction "IO_L20N_T3_16_B22") (pintype "bidirectional"))
    )
    (net (code "207") (name "/TX1_TMDS2_N") (class "Default")
      (node (ref "U10F") (pin "B21") (pinfunction "IO_L21P_T3_DQS_16_B21") (pintype "bidirectional"))
    )
    (net (code "208") (name "/TX1_TMDS2_P") (class "Default")
      (node (ref "U10F") (pin "A21") (pinfunction "IO_L21N_T3_DQS_16_A21") (pintype "bidirectional"))
    )
    (net (code "209") (name "/UART0_RX") (class "Default")
      (node (ref "U10F") (pin "E13") (pinfunction "IO_L4P_T0_16_E13") (pintype "bidirectional"))
    )
    (net (code "210") (name "/UART0_TX") (class "Default")
      (node (ref "U10F") (pin "E14") (pinfunction "IO_L4N_T0_16_E14") (pintype "bidirectional"))
    )
    (net (code "211") (name "/WAKE#") (class "Default")
      (node (ref "U10F") (pin "D20") (pinfunction "IO_L19P_T3_16_D20") (pintype "bidirectional"))
    )
    (net (code "212") (name "GND") (class "Default")
      (node (ref "C10F") (pin "2") (pinfunction "2_2") (pintype "passive"))
      (node (ref "C11F") (pin "2") (pinfunction "2_2") (pintype "passive"))
      (node (ref "C12F") (pin "2") (pinfunction "2_2") (pintype "passive"))
      (node (ref "C13F") (pin "2") (pinfunction "2_2") (pintype "passive"))
      (node (ref "C14F") (pin "2") (pinfunction "2_2") (pintype "passive"))
      (node (ref "C15F") (pin "2") (pinfunction "2_2") (pintype "passive"))
      (node (ref "C16F") (pin "2") (pinfunction "2_2") (pintype "passive"))
      (node (ref "C17F") (pin "2") (pinfunction "2_2") (pintype "passive"))
      (node (ref "C18F") (pin "2") (pinfunction "2_2") (pintype "passive"))
      (node (ref "C19F") (pin "2") (pinfunction "2_2") (pintype "passive"))
      (node (ref "C26F") (pin "2") (pinfunction "2_2") (pintype "passive"))
      (node (ref "C28F") (pin "2") (pinfunction "2_2") (pintype "passive"))
      (node (ref "C29F") (pin "2") (pinfunction "2_2") (pintype "passive"))
      (node (ref "C30F") (pin "2") (pinfunction "2_2") (pintype "passive"))
      (node (ref "C31F") (pin "2") (pinfunction "2_2") (pintype "passive"))
      (node (ref "C32F") (pin "2") (pinfunction "2_2") (pintype "passive"))
      (node (ref "C33F") (pin "2") (pinfunction "2_2") (pintype "passive"))
      (node (ref "C34F") (pin "2") (pinfunction "2_2") (pintype "passive"))
      (node (ref "C35F") (pin "2") (pinfunction "2_2") (pintype "passive"))
      (node (ref "C38F") (pin "2") (pinfunction "2_2") (pintype "passive"))
      (node (ref "C39F") (pin "2") (pinfunction "2_2") (pintype "passive"))
      (node (ref "C41F") (pin "2") (pinfunction "2_2") (pintype "passive"))
      (node (ref "C42F") (pin "2") (pinfunction "2_2") (pintype "passive"))
      (node (ref "C43F") (pin "2") (pinfunction "2_2") (pintype "passive"))
      (node (ref "C44F") (pin "2") (pinfunction "2_2") (pintype "passive"))
      (node (ref "C45F") (pin "2") (pinfunction "2_2") (pintype "passive"))
      (node (ref "C46F") (pin "2") (pinfunction "2_2") (pintype "passive"))
      (node (ref "C47F") (pin "2") (pinfunction "2_2") (pintype "passive"))
      (node (ref "C48F") (pin "2") (pinfunction "2_2") (pintype "passive"))
      (node (ref "C49F") (pin "2") (pinfunction "2_2") (pintype "passive"))
      (node (ref "C50F") (pin "2") (pinfunction "2_2") (pintype "passive"))
      (node (ref "C51F") (pin "2") (pinfunction "2_2") (pintype "passive"))
      (node (ref "C52F") (pin "2") (pinfunction "2_2") (pintype "passive"))
      (node (ref "C53F") (pin "2") (pinfunction "2_2") (pintype "passive"))
      (node (ref "C54F") (pin "2") (pinfunction "2_2") (pintype "passive"))
      (node (ref "C55F") (pin "2") (pinfunction "2_2") (pintype "passive"))
      (node (ref "C56F") (pin "2") (pinfunction "2_2") (pintype "passive"))
      (node (ref "C57F") (pin "2") (pinfunction "2_2") (pintype "passive"))
      (node (ref "C58F") (pin "2") (pinfunction "2_2") (pintype "passive"))
      (node (ref "C59F") (pin "2") (pinfunction "2_2") (pintype "passive"))
      (node (ref "C60F") (pin "2") (pinfunction "2_2") (pintype "passive"))
      (node (ref "C61F") (pin "2") (pinfunction "2_2") (pintype "passive"))
      (node (ref "C62F") (pin "2") (pinfunction "2_2") (pintype "passive"))
      (node (ref "C63F") (pin "2") (pinfunction "2_2") (pintype "passive"))
      (node (ref "C64F") (pin "2") (pinfunction "2_2") (pintype "passive"))
      (node (ref "C65F") (pin "2") (pinfunction "2_2") (pintype "passive"))
      (node (ref "C66F") (pin "2") (pinfunction "2_2") (pintype "passive"))
      (node (ref "C67F") (pin "2") (pinfunction "2_2") (pintype "passive"))
      (node (ref "C68F") (pin "2") (pinfunction "2_2") (pintype "passive"))
      (node (ref "C69F") (pin "2") (pinfunction "2_2") (pintype "passive"))
      (node (ref "C70F") (pin "2") (pinfunction "2_2") (pintype "passive"))
      (node (ref "C71F") (pin "2") (pinfunction "2_2") (pintype "passive"))
      (node (ref "C72F") (pin "2") (pinfunction "2_2") (pintype "passive"))
      (node (ref "C73F") (pin "2") (pinfunction "2_2") (pintype "passive"))
      (node (ref "C74F") (pin "2") (pinfunction "2_2") (pintype "passive"))
      (node (ref "C75F") (pin "2") (pinfunction "2_2") (pintype "passive"))
      (node (ref "C76F") (pin "2") (pinfunction "2_2") (pintype "passive"))
      (node (ref "C77F") (pin "2") (pinfunction "2_2") (pintype "passive"))
      (node (ref "C78F") (pin "2") (pinfunction "2_2") (pintype "passive"))
      (node (ref "C79F") (pin "2") (pinfunction "2_2") (pintype "passive"))
      (node (ref "C80F") (pin "2") (pinfunction "2_2") (pintype "passive"))
      (node (ref "C81F") (pin "2") (pinfunction "2_2") (pintype "passive"))
      (node (ref "C82F") (pin "2") (pinfunction "2_2") (pintype "passive"))
      (node (ref "C83F") (pin "2") (pinfunction "2_2") (pintype "passive"))
      (node (ref "C84F") (pin "2") (pinfunction "2_2") (pintype "passive"))
      (node (ref "C85F") (pin "2") (pinfunction "2_2") (pintype "passive"))
      (node (ref "C86F") (pin "2") (pinfunction "2_2") (pintype "passive"))
      (node (ref "C87F") (pin "2") (pinfunction "2_2") (pintype "passive"))
      (node (ref "C88F") (pin "2") (pinfunction "2_2") (pintype "passive"))
      (node (ref "C89F") (pin "2") (pinfunction "2_2") (pintype "passive"))
      (node (ref "C90F") (pin "2") (pinfunction "2_2") (pintype "passive"))
      (node (ref "C91F") (pin "2") (pinfunction "2_2") (pintype "passive"))
      (node (ref "C92F") (pin "2") (pinfunction "2_2") (pintype "passive"))
      (node (ref "C93F") (pin "2") (pinfunction "2_2") (pintype "passive"))
      (node (ref "C94F") (pin "2") (pinfunction "2_2") (pintype "passive"))
      (node (ref "C95F") (pin "2") (pinfunction "2_2") (pintype "passive"))
      (node (ref "C96F") (pin "2") (pinfunction "2_2") (pintype "passive"))
      (node (ref "C97F") (pin "2") (pinfunction "2_2") (pintype "passive"))
      (node (ref "C98F") (pin "2") (pinfunction "2_2") (pintype "passive"))
      (node (ref "C99F") (pin "2") (pinfunction "2_2") (pintype "passive"))
      (node (ref "R10F") (pin "2") (pinfunction "2_2") (pintype "passive"))
      (node (ref "R15F") (pin "1") (pinfunction "1_1") (pintype "passive"))
      (node (ref "U10F") (pin "A11") (pinfunction "GND_A11") (pintype "power_in"))
      (node (ref "U10F") (pin "A12") (pinfunction "GND_A12") (pintype "power_in"))
      (node (ref "U10F") (pin "A2") (pinfunction "GND_A2") (pintype "power_in"))
      (node (ref "U10F") (pin "A22") (pinfunction "GND_A22") (pintype "power_in"))
      (node (ref "U10F") (pin "A3") (pinfunction "GND_A3") (pintype "power_in"))
      (node (ref "U10F") (pin "A5") (pinfunction "GND_A5") (pintype "power_in"))
      (node (ref "U10F") (pin "A7") (pinfunction "GND_A7") (pintype "power_in"))
      (node (ref "U10F") (pin "A9") (pinfunction "GND_A9") (pintype "power_in"))
      (node (ref "U10F") (pin "AA12") (pinfunction "GND_AA12") (pintype "power_in"))
      (node (ref "U10F") (pin "AA2") (pinfunction "GND_AA2") (pintype "power_in"))
      (node (ref "U10F") (pin "AA22") (pinfunction "GND_AA22") (pintype "power_in"))
      (node (ref "U10F") (pin "AB19") (pinfunction "GND_AB19") (pintype "power_in"))
      (node (ref "U10F") (pin "AB9") (pinfunction "GND_AB9") (pintype "power_in"))
      (node (ref "U10F") (pin "B12") (pinfunction "GND_B12") (pintype "power_in"))
      (node (ref "U10F") (pin "B19") (pinfunction "GND_B19") (pintype "power_in"))
      (node (ref "U10F") (pin "B3") (pinfunction "GND_B3") (pintype "power_in"))
      (node (ref "U10F") (pin "C10") (pinfunction "GND_C10") (pintype "power_in"))
      (node (ref "U10F") (pin "C12") (pinfunction "GND_C12") (pintype "power_in"))
      (node (ref "U10F") (pin "C16") (pinfunction "GND_C16") (pintype "power_in"))
      (node (ref "U10F") (pin "C3") (pinfunction "GND_C3") (pintype "power_in"))
      (node (ref "U10F") (pin "C6") (pinfunction "GND_C6") (pintype "power_in"))
      (node (ref "U10F") (pin "D12") (pinfunction "GND_D12") (pintype "power_in"))
      (node (ref "U10F") (pin "D13") (pinfunction "GND_D13") (pintype "power_in"))
      (node (ref "U10F") (pin "D3") (pinfunction "GND_D3") (pintype "power_in"))
      (node (ref "U10F") (pin "D4") (pinfunction "GND_D4") (pintype "power_in"))
      (node (ref "U10F") (pin "D8") (pinfunction "GND_D8") (pintype "power_in"))
      (node (ref "U10F") (pin "E11") (pinfunction "GND_E11") (pintype "power_in"))
      (node (ref "U10F") (pin "E20") (pinfunction "GND_E20") (pintype "power_in"))
      (node (ref "U10F") (pin "E4") (pinfunction "GND_E4") (pintype "power_in"))
      (node (ref "U10F") (pin "E5") (pinfunction "GND_E5") (pintype "power_in"))
      (node (ref "U10F") (pin "E7") (pinfunction "GND_E7") (pintype "power_in"))
      (node (ref "U10F") (pin "E9") (pinfunction "GND_E9") (pintype "power_in"))
      (node (ref "U10F") (pin "F11") (pinfunction "GND_F11") (pintype "power_in"))
      (node (ref "U10F") (pin "F17") (pinfunction "GND_F17") (pintype "power_in"))
      (node (ref "U10F") (pin "F5") (pinfunction "GND_F5") (pintype "power_in"))
      (node (ref "U10F") (pin "G10") (pinfunction "GND_G10") (pintype "power_in"))
      (node (ref "U10F") (pin "G12") (pinfunction "GND_G12") (pintype "power_in"))
      (node (ref "U10F") (pin "G14") (pinfunction "GND_G14") (pintype "power_in"))
      (node (ref "U10F") (pin "G5") (pinfunction "GND_G5") (pintype "power_in"))
      (node (ref "U10F") (pin "G6") (pinfunction "GND_G6") (pintype "power_in"))
      (node (ref "U10F") (pin "G7") (pinfunction "GND_G7") (pintype "power_in"))
      (node (ref "U10F") (pin "G8") (pinfunction "GND_G8") (pintype "power_in"))
      (node (ref "U10F") (pin "G9") (pinfunction "GND_G9") (pintype "power_in"))
      (node (ref "U10F") (pin "H1") (pinfunction "GND_H1") (pintype "power_in"))
      (node (ref "U10F") (pin "H11") (pinfunction "GND_H11") (pintype "power_in"))
      (node (ref "U10F") (pin "H21") (pinfunction "GND_H21") (pintype "power_in"))
      (node (ref "U10F") (pin "H7") (pinfunction "GND_H7") (pintype "power_in"))
      (node (ref "U10F") (pin "H9") (pinfunction "GND_H9") (pintype "power_in"))
      (node (ref "U10F") (pin "J10") (pinfunction "GND_J10") (pintype "power_in"))
      (node (ref "U10F") (pin "J12") (pinfunction "GND_J12") (pintype "power_in"))
      (node (ref "U10F") (pin "J18") (pinfunction "GND_J18") (pintype "power_in"))
      (node (ref "U10F") (pin "J8") (pinfunction "GND_J8") (pintype "power_in"))
      (node (ref "U10F") (pin "K11") (pinfunction "GND_K11") (pintype "power_in"))
      (node (ref "U10F") (pin "K15") (pinfunction "GND_K15") (pintype "power_in"))
      (node (ref "U10F") (pin "K5") (pinfunction "GND_K5") (pintype "power_in"))
      (node (ref "U10F") (pin "K7") (pinfunction "GND_K7") (pintype "power_in"))
      (node (ref "U10F") (pin "K9") (pinfunction "GNDADC_0_K9") (pintype "power_in"))
      (node (ref "U10F") (pin "L10") (pinfunction "VP_0_L10") (pintype "input"))
      (node (ref "U10F") (pin "L2") (pinfunction "GND_L2") (pintype "power_in"))
      (node (ref "U10F") (pin "L22") (pinfunction "GND_L22") (pintype "power_in"))
      (node (ref "U10F") (pin "L8") (pinfunction "GND_L8") (pintype "power_in"))
      (node (ref "U10F") (pin "L9") (pinfunction "VREFN_0_L9") (pintype "input"))
      (node (ref "U10F") (pin "M10") (pinfunction "VREFP_0_M10") (pintype "input"))
      (node (ref "U10F") (pin "M11") (pinfunction "GND_M11") (pintype "power_in"))
      (node (ref "U10F") (pin "M19") (pinfunction "GND_M19") (pintype "power_in"))
      (node (ref "U10F") (pin "M7") (pinfunction "GND_M7") (pintype "power_in"))
      (node (ref "U10F") (pin "M9") (pinfunction "VN_0_M9") (pintype "input"))
      (node (ref "U10F") (pin "N10") (pinfunction "DXP_0_N10") (pintype "input"))
      (node (ref "U10F") (pin "N16") (pinfunction "GND_N16") (pintype "power_in"))
      (node (ref "U10F") (pin "N6") (pinfunction "GND_N6") (pintype "power_in"))
      (node (ref "U10F") (pin "N8") (pinfunction "GND_N8") (pintype "power_in"))
      (node (ref "U10F") (pin "N9") (pinfunction "DXN_0_N9") (pintype "input"))
      (node (ref "U10F") (pin "P11") (pinfunction "GND_P11") (pintype "power_in"))
      (node (ref "U10F") (pin "P13") (pinfunction "GND_P13") (pintype "power_in"))
      (node (ref "U10F") (pin "P3") (pinfunction "GND_P3") (pintype "power_in"))
      (node (ref "U10F") (pin "P7") (pinfunction "GND_P7") (pintype "power_in"))
      (node (ref "U10F") (pin "P9") (pinfunction "GND_P9") (pintype "power_in"))
      (node (ref "U10F") (pin "R10") (pinfunction "GND_R10") (pintype "power_in"))
      (node (ref "U10F") (pin "R12") (pinfunction "GND_R12") (pintype "power_in"))
      (node (ref "U10F") (pin "R20") (pinfunction "GND_R20") (pintype "power_in"))
      (node (ref "U10F") (pin "R8") (pinfunction "GND_R8") (pintype "power_in"))
      (node (ref "U10F") (pin "T11") (pinfunction "GND_T11") (pintype "power_in"))
      (node (ref "U10F") (pin "T17") (pinfunction "GND_T17") (pintype "power_in"))
      (node (ref "U10F") (pin "T7") (pinfunction "GND_T7") (pintype "power_in"))
      (node (ref "U10F") (pin "T9") (pinfunction "GND_T9") (pintype "power_in"))
      (node (ref "U10F") (pin "U10") (pinfunction "M1_0_U10") (pintype "input"))
      (node (ref "U10F") (pin "U14") (pinfunction "GND_U14") (pintype "power_in"))
      (node (ref "U10F") (pin "U4") (pinfunction "GND_U4") (pintype "power_in"))
      (node (ref "U10F") (pin "V1") (pinfunction "GND_V1") (pintype "power_in"))
      (node (ref "U10F") (pin "V11") (pinfunction "GND_V11") (pintype "power_in"))
      (node (ref "U10F") (pin "V21") (pinfunction "GND_V21") (pintype "power_in"))
      (node (ref "U10F") (pin "W18") (pinfunction "GND_W18") (pintype "power_in"))
      (node (ref "U10F") (pin "W8") (pinfunction "GND_W8") (pintype "power_in"))
      (node (ref "U10F") (pin "Y15") (pinfunction "GND_Y15") (pintype "power_in"))
      (node (ref "U10F") (pin "Y5") (pinfunction "GND_Y5") (pintype "power_in"))
      (node (ref "U11F") (pin "2") (pinfunction "GND_2") (pintype "power_in"))
    )
    (net (code "213") (name "Net-(U10FG-MGTRREF_216)") (class "Default")
      (node (ref "R11F") (pin "1") (pinfunction "1_1") (pintype "passive"))
      (node (ref "U10F") (pin "F8") (pinfunction "MGTRREF_216_F8") (pintype "input"))
    )
    (net (code "214") (name "P1.0V") (class "Default")
      (node (ref "C10F") (pin "1") (pinfunction "1_1") (pintype "passive"))
      (node (ref "C11F") (pin "1") (pinfunction "1_1") (pintype "passive"))
      (node (ref "C12F") (pin "1") (pinfunction "1_1") (pintype "passive"))
      (node (ref "C38F") (pin "1") (pinfunction "1_1") (pintype "passive"))
      (node (ref "C39F") (pin "1") (pinfunction "1_1") (pintype "passive"))
      (node (ref "C41F") (pin "1") (pinfunction "1_1") (pintype "passive"))
      (node (ref "C42F") (pin "1") (pinfunction "1_1") (pintype "passive"))
      (node (ref "C43F") (pin "1") (pinfunction "1_1") (pintype "passive"))
      (node (ref "C44F") (pin "1") (pinfunction "1_1") (pintype "passive"))
      (node (ref "C45F") (pin "1") (pinfunction "1_1") (pintype "passive"))
      (node (ref "C46F") (pin "1") (pinfunction "1_1") (pintype "passive"))
      (node (ref "C47F") (pin "1") (pinfunction "1_1") (pintype "passive"))
      (node (ref "C48F") (pin "1") (pinfunction "1_1") (pintype "passive"))
      (node (ref "C49F") (pin "1") (pinfunction "1_1") (pintype "passive"))
      (node (ref "U10F") (pin "D10") (pinfunction "MGTAVCC_D10") (pintype "power_in"))
      (node (ref "U10F") (pin "D6") (pinfunction "MGTAVCC_D6") (pintype "power_in"))
      (node (ref "U10F") (pin "E8") (pinfunction "MGTAVCC_E8") (pintype "power_in"))
      (node (ref "U10F") (pin "F7") (pinfunction "MGTAVCC_F7") (pintype "power_in"))
      (node (ref "U10F") (pin "F9") (pinfunction "MGTAVCC_F9") (pintype "power_in"))
      (node (ref "U10F") (pin "H10") (pinfunction "VCCINT_H10") (pintype "power_in"))
      (node (ref "U10F") (pin "H8") (pinfunction "VCCINT_H8") (pintype "power_in"))
      (node (ref "U10F") (pin "J11") (pinfunction "VCCBRAM_J11") (pintype "power_in"))
      (node (ref "U10F") (pin "J7") (pinfunction "VCCINT_J7") (pintype "power_in"))
      (node (ref "U10F") (pin "J9") (pinfunction "VCCINT_J9") (pintype "power_in"))
      (node (ref "U10F") (pin "K8") (pinfunction "VCCINT_K8") (pintype "power_in"))
      (node (ref "U10F") (pin "L11") (pinfunction "VCCBRAM_L11") (pintype "power_in"))
      (node (ref "U10F") (pin "L7") (pinfunction "VCCINT_L7") (pintype "power_in"))
      (node (ref "U10F") (pin "M8") (pinfunction "VCCINT_M8") (pintype "power_in"))
      (node (ref "U10F") (pin "N11") (pinfunction "VCCBRAM_N11") (pintype "power_in"))
      (node (ref "U10F") (pin "N7") (pinfunction "VCCINT_N7") (pintype "power_in"))
      (node (ref "U10F") (pin "P10") (pinfunction "VCCINT_P10") (pintype "power_in"))
      (node (ref "U10F") (pin "P8") (pinfunction "VCCINT_P8") (pintype "power_in"))
      (node (ref "U10F") (pin "R7") (pinfunction "VCCINT_R7") (pintype "power_in"))
      (node (ref "U10F") (pin "R9") (pinfunction "VCCINT_R9") (pintype "power_in"))
      (node (ref "U10F") (pin "T10") (pinfunction "VCCINT_T10") (pintype "power_in"))
      (node (ref "U10F") (pin "T8") (pinfunction "VCCINT_T8") (pintype "power_in"))
    )
    (net (code "215") (name "P1.2VTT") (class "Default")
      (node (ref "C15F") (pin "1") (pinfunction "1_1") (pintype "passive"))
      (node (ref "C16F") (pin "1") (pinfunction "1_1") (pintype "passive"))
      (node (ref "C17F") (pin "1") (pinfunction "1_1") (pintype "passive"))
      (node (ref "C87F") (pin "1") (pinfunction "1_1") (pintype "passive"))
      (node (ref "C88F") (pin "1") (pinfunction "1_1") (pintype "passive"))
      (node (ref "R11F") (pin "2") (pinfunction "2_2") (pintype "passive"))
      (node (ref "U10F") (pin "B11") (pinfunction "MGTAVTT_B11") (pintype "power_in"))
      (node (ref "U10F") (pin "B5") (pinfunction "MGTAVTT_B5") (pintype "power_in"))
      (node (ref "U10F") (pin "B7") (pinfunction "MGTAVTT_B7") (pintype "power_in"))
      (node (ref "U10F") (pin "B9") (pinfunction "MGTAVTT_B9") (pintype "power_in"))
      (node (ref "U10F") (pin "C4") (pinfunction "MGTAVTT_C4") (pintype "power_in"))
      (node (ref "U10F") (pin "C8") (pinfunction "MGTAVTT_C8") (pintype "power_in"))
    )
    (net (code "216") (name "P1.5V_D") (class "Default")
      (node (ref "C59F") (pin "1") (pinfunction "1_1") (pintype "passive"))
      (node (ref "C60F") (pin "1") (pinfunction "1_1") (pintype "passive"))
      (node (ref "C61F") (pin "1") (pinfunction "1_1") (pintype "passive"))
      (node (ref "C62F") (pin "1") (pinfunction "1_1") (pintype "passive"))
      (node (ref "C63F") (pin "1") (pinfunction "1_1") (pintype "passive"))
      (node (ref "C64F") (pin "1") (pinfunction "1_1") (pintype "passive"))
      (node (ref "C65F") (pin "1") (pinfunction "1_1") (pintype "passive"))
      (node (ref "C73F") (pin "1") (pinfunction "1_1") (pintype "passive"))
      (node (ref "C74F") (pin "1") (pinfunction "1_1") (pintype "passive"))
      (node (ref "C75F") (pin "1") (pinfunction "1_1") (pintype "passive"))
      (node (ref "C76F") (pin "1") (pinfunction "1_1") (pintype "passive"))
      (node (ref "C77F") (pin "1") (pinfunction "1_1") (pintype "passive"))
      (node (ref "C78F") (pin "1") (pinfunction "1_1") (pintype "passive"))
      (node (ref "C79F") (pin "1") (pinfunction "1_1") (pintype "passive"))
      (node (ref "U10F") (pin "AA7") (pinfunction "VCCO_34_AA7") (pintype "power_in"))
      (node (ref "U10F") (pin "AB4") (pinfunction "VCCO_34_AB4") (pintype "power_in"))
      (node (ref "U10F") (pin "C1") (pinfunction "VCCO_35_C1") (pintype "power_in"))
      (node (ref "U10F") (pin "F2") (pinfunction "VCCO_35_F2") (pintype "power_in"))
      (node (ref "U10F") (pin "H6") (pinfunction "VCCO_35_H6") (pintype "power_in"))
      (node (ref "U10F") (pin "J3") (pinfunction "VCCO_35_J3") (pintype "power_in"))
      (node (ref "U10F") (pin "M4") (pinfunction "VCCO_35_M4") (pintype "power_in"))
      (node (ref "U10F") (pin "N1") (pinfunction "VCCO_35_N1") (pintype "power_in"))
      (node (ref "U10F") (pin "R5") (pinfunction "VCCO_34_R5") (pintype "power_in"))
      (node (ref "U10F") (pin "T2") (pinfunction "VCCO_34_T2") (pintype "power_in"))
      (node (ref "U10F") (pin "V6") (pinfunction "VCCO_34_V6") (pintype "power_in"))
      (node (ref "U10F") (pin "W3") (pinfunction "VCCO_34_W3") (pintype "power_in"))
    )
    (net (code "217") (name "P1.8V") (class "Default")
      (node (ref "C26F") (pin "1") (pinfunction "1_1") (pintype "passive"))
      (node (ref "C28F") (pin "1") (pinfunction "1_1") (pintype "passive"))
      (node (ref "C29F") (pin "1") (pinfunction "1_1") (pintype "passive"))
      (node (ref "C30F") (pin "1") (pinfunction "1_1") (pintype "passive"))
      (node (ref "C31F") (pin "1") (pinfunction "1_1") (pintype "passive"))
      (node (ref "C32F") (pin "1") (pinfunction "1_1") (pintype "passive"))
      (node (ref "C33F") (pin "1") (pinfunction "1_1") (pintype "passive"))
      (node (ref "C34F") (pin "1") (pinfunction "1_1") (pintype "passive"))
      (node (ref "C35F") (pin "1") (pinfunction "1_1") (pintype "passive"))
      (node (ref "U10F") (pin "E12") (pinfunction "VCCBATT_0_E12") (pintype "power_in"))
      (node (ref "U10F") (pin "H12") (pinfunction "VCCAUX_H12") (pintype "power_in"))
      (node (ref "U10F") (pin "K10") (pinfunction "VCCADC_0_K10") (pintype "power_in"))
      (node (ref "U10F") (pin "K12") (pinfunction "VCCAUX_K12") (pintype "power_in"))
      (node (ref "U10F") (pin "M12") (pinfunction "VCCAUX_M12") (pintype "power_in"))
      (node (ref "U10F") (pin "P12") (pinfunction "VCCAUX_P12") (pintype "power_in"))
      (node (ref "U10F") (pin "R11") (pinfunction "VCCAUX_R11") (pintype "power_in"))
    )
    (net (code "218") (name "P3.3V") (class "Default")
      (node (ref "C50F") (pin "1") (pinfunction "1_1") (pintype "passive"))
      (node (ref "C51F") (pin "1") (pinfunction "1_1") (pintype "passive"))
      (node (ref "C52F") (pin "1") (pinfunction "1_1") (pintype "passive"))
      (node (ref "C53F") (pin "1") (pinfunction "1_1") (pintype "passive"))
      (node (ref "C54F") (pin "1") (pinfunction "1_1") (pintype "passive"))
      (node (ref "C55F") (pin "1") (pinfunction "1_1") (pintype "passive"))
      (node (ref "C56F") (pin "1") (pinfunction "1_1") (pintype "passive"))
      (node (ref "C57F") (pin "1") (pinfunction "1_1") (pintype "passive"))
      (node (ref "C58F") (pin "1") (pinfunction "1_1") (pintype "passive"))
      (node (ref "C66F") (pin "1") (pinfunction "1_1") (pintype "passive"))
      (node (ref "C67F") (pin "1") (pinfunction "1_1") (pintype "passive"))
      (node (ref "C68F") (pin "1") (pinfunction "1_1") (pintype "passive"))
      (node (ref "C69F") (pin "1") (pinfunction "1_1") (pintype "passive"))
      (node (ref "C70F") (pin "1") (pinfunction "1_1") (pintype "passive"))
      (node (ref "C71F") (pin "1") (pinfunction "1_1") (pintype "passive"))
      (node (ref "C72F") (pin "1") (pinfunction "1_1") (pintype "passive"))
      (node (ref "C80F") (pin "1") (pinfunction "1_1") (pintype "passive"))
      (node (ref "C81F") (pin "1") (pinfunction "1_1") (pintype "passive"))
      (node (ref "C82F") (pin "1") (pinfunction "1_1") (pintype "passive"))
      (node (ref "C83F") (pin "1") (pinfunction "1_1") (pintype "passive"))
      (node (ref "C84F") (pin "1") (pinfunction "1_1") (pintype "passive"))
      (node (ref "C85F") (pin "1") (pinfunction "1_1") (pintype "passive"))
      (node (ref "C86F") (pin "1") (pinfunction "1_1") (pintype "passive"))
      (node (ref "C89F") (pin "1") (pinfunction "1_1") (pintype "passive"))
      (node (ref "C90F") (pin "1") (pinfunction "1_1") (pintype "passive"))
      (node (ref "C91F") (pin "1") (pinfunction "1_1") (pintype "passive"))
      (node (ref "C92F") (pin "1") (pinfunction "1_1") (pintype "passive"))
      (node (ref "C93F") (pin "1") (pinfunction "1_1") (pintype "passive"))
      (node (ref "C94F") (pin "1") (pinfunction "1_1") (pintype "passive"))
      (node (ref "C95F") (pin "1") (pinfunction "1_1") (pintype "passive"))
      (node (ref "C96F") (pin "1") (pinfunction "1_1") (pintype "passive"))
      (node (ref "C97F") (pin "1") (pinfunction "1_1") (pintype "passive"))
      (node (ref "C98F") (pin "1") (pinfunction "1_1") (pintype "passive"))
      (node (ref "C99F") (pin "1") (pinfunction "1_1") (pintype "passive"))
      (node (ref "P10F") (pin "2") (pinfunction "2_2") (pintype "passive"))
      (node (ref "R12F") (pin "2") (pinfunction "2_2") (pintype "passive"))
      (node (ref "R13F") (pin "2") (pinfunction "2_2") (pintype "passive"))
      (node (ref "R14F") (pin "2") (pinfunction "2_2") (pintype "passive"))
      (node (ref "U10F") (pin "A17") (pinfunction "VCCO_16_A17") (pintype "power_in"))
      (node (ref "U10F") (pin "AA17") (pinfunction "VCCO_13_AA17") (pintype "power_in"))
      (node (ref "U10F") (pin "AB14") (pinfunction "VCCO_13_AB14") (pintype "power_in"))
      (node (ref "U10F") (pin "B14") (pinfunction "VCCO_16_B14") (pintype "power_in"))
      (node (ref "U10F") (pin "C21") (pinfunction "VCCO_16_C21") (pintype "power_in"))
      (node (ref "U10F") (pin "D18") (pinfunction "VCCO_16_D18") (pintype "power_in"))
      (node (ref "U10F") (pin "E15") (pinfunction "VCCO_16_E15") (pintype "power_in"))
      (node (ref "U10F") (pin "F12") (pinfunction "VCCO_0_F12") (pintype "power_in"))
      (node (ref "U10F") (pin "F22") (pinfunction "VCCO_16_F22") (pintype "power_in"))
      (node (ref "U10F") (pin "G19") (pinfunction "VCCO_15_G19") (pintype "power_in"))
      (node (ref "U10F") (pin "H16") (pinfunction "VCCO_15_H16") (pintype "power_in"))
      (node (ref "U10F") (pin "J13") (pinfunction "VCCO_15_J13") (pintype "power_in"))
      (node (ref "U10F") (pin "K20") (pinfunction "VCCO_15_K20") (pintype "power_in"))
      (node (ref "U10F") (pin "L17") (pinfunction "VCCO_15_L17") (pintype "power_in"))
      (node (ref "U10F") (pin "M14") (pinfunction "VCCO_14_M14") (pintype "power_in"))
      (node (ref "U10F") (pin "N21") (pinfunction "VCCO_15_N21") (pintype "power_in"))
      (node (ref "U10F") (pin "P18") (pinfunction "VCCO_14_P18") (pintype "power_in"))
      (node (ref "U10F") (pin "R15") (pinfunction "VCCO_14_R15") (pintype "power_in"))
      (node (ref "U10F") (pin "T12") (pinfunction "VCCO_0_T12") (pintype "power_in"))
      (node (ref "U10F") (pin "T22") (pinfunction "VCCO_14_T22") (pintype "power_in"))
      (node (ref "U10F") (pin "U11") (pinfunction "M0_0_U11") (pintype "input"))
      (node (ref "U10F") (pin "U19") (pinfunction "VCCO_14_U19") (pintype "power_in"))
      (node (ref "U10F") (pin "U8") (pinfunction "CFGBVS_0_U8") (pintype "input"))
      (node (ref "U10F") (pin "V16") (pinfunction "VCCO_13_V16") (pintype "power_in"))
      (node (ref "U10F") (pin "W13") (pinfunction "VCCO_13_W13") (pintype "power_in"))
      (node (ref "U10F") (pin "Y10") (pinfunction "VCCO_13_Y10") (pintype "power_in"))
      (node (ref "U10F") (pin "Y20") (pinfunction "VCCO_14_Y20") (pintype "power_in"))
      (node (ref "U11F") (pin "1") (pinfunction "OE_1") (pintype "passive"))
      (node (ref "U11F") (pin "4") (pinfunction "Vcc_4") (pintype "power_in"))
    )
    (net (code "219") (name "VTT_REF") (class "Default")
      (node (ref "C13F") (pin "1") (pinfunction "1_1") (pintype "passive"))
      (node (ref "C14F") (pin "1") (pinfunction "1_1") (pintype "passive"))
      (node (ref "C18F") (pin "1") (pinfunction "1_1") (pintype "passive"))
      (node (ref "C19F") (pin "1") (pinfunction "1_1") (pintype "passive"))
      (node (ref "U10F") (pin "E3") (pinfunction "IO_L6N_T0_VREF_35_E3") (pintype "bidirectional"))
      (node (ref "U10F") (pin "N3") (pinfunction "IO_L19N_T3_VREF_35_N3") (pintype "bidirectional"))
      (node (ref "U10F") (pin "V3") (pinfunction "IO_L6N_T0_VREF_34_V3") (pintype "bidirectional"))
      (node (ref "U10F") (pin "W7") (pinfunction "IO_L19N_T3_VREF_34_W7") (pintype "bidirectional"))
    )
    (net (code "220") (name "unconnected-(U10FA-IO_25_14-PadN15)") (class "Default")
      (node (ref "U10F") (pin "N15") (pinfunction "IO_25_14_N15") (pintype "bidirectional"))
    )
    (net (code "221") (name "unconnected-(U10FA-IO_L3N_T0_DQS_EMCCLK_14-PadV22)") (class "Default")
      (node (ref "U10F") (pin "V22") (pinfunction "IO_L3N_T0_DQS_EMCCLK_14_V22") (pintype "bidirectional"))
    )
    (net (code "222") (name "unconnected-(U10FA-IO_L6N_T0_D08_VREF_14-PadT20)") (class "Default")
      (node (ref "U10F") (pin "T20") (pinfunction "IO_L6N_T0_D08_VREF_14_T20") (pintype "bidirectional"))
    )
    (net (code "223") (name "unconnected-(U10FA-IO_L8P_T1_D11_14-PadAA20)") (class "Default")
      (node (ref "U10F") (pin "AA20") (pinfunction "IO_L8P_T1_D11_14_AA20") (pintype "bidirectional"))
    )
    (net (code "224") (name "unconnected-(U10FA-IO_L9N_T1_DQS_D13_14-PadY22)") (class "Default")
      (node (ref "U10F") (pin "Y22") (pinfunction "IO_L9N_T1_DQS_D13_14_Y22") (pintype "bidirectional"))
    )
    (net (code "225") (name "unconnected-(U10FA-IO_L9P_T1_DQS_14-PadY21)") (class "Default")
      (node (ref "U10F") (pin "Y21") (pinfunction "IO_L9P_T1_DQS_14_Y21") (pintype "bidirectional"))
    )
    (net (code "226") (name "unconnected-(U10FA-IO_L14N_T2_SRCC_14-PadV19)") (class "Default")
      (node (ref "U10F") (pin "V19") (pinfunction "IO_L14N_T2_SRCC_14_V19") (pintype "bidirectional"))
    )
    (net (code "227") (name "unconnected-(U10FA-IO_L19N_T3_A09_D25_VREF_14-PadR14)") (class "Default")
      (node (ref "U10F") (pin "R14") (pinfunction "IO_L19N_T3_A09_D25_VREF_14_R14") (pintype "bidirectional"))
    )
    (net (code "228") (name "unconnected-(U10FA-IO_L19P_T3_A10_D26_14-PadP14)") (class "Default")
      (node (ref "U10F") (pin "P14") (pinfunction "IO_L19P_T3_A10_D26_14_P14") (pintype "bidirectional"))
    )
    (net (code "229") (name "unconnected-(U10FA-IO_L20P_T3_A08_D24_14-PadR18)") (class "Default")
      (node (ref "U10F") (pin "R18") (pinfunction "IO_L20P_T3_A08_D24_14_R18") (pintype "bidirectional"))
    )
    (net (code "230") (name "unconnected-(U10FA-IO_L21P_T3_DQS_14-PadN17)") (class "Default")
      (node (ref "U10F") (pin "N17") (pinfunction "IO_L21P_T3_DQS_14_N17") (pintype "bidirectional"))
    )
    (net (code "231") (name "unconnected-(U10FA-IO_L22P_T3_A05_D21_14-PadP15)") (class "Default")
      (node (ref "U10F") (pin "P15") (pinfunction "IO_L22P_T3_A05_D21_14_P15") (pintype "bidirectional"))
    )
    (net (code "232") (name "unconnected-(U10FA-IO_L23N_T3_A02_D18_14-PadN14)") (class "Default")
      (node (ref "U10F") (pin "N14") (pinfunction "IO_L23N_T3_A02_D18_14_N14") (pintype "bidirectional"))
    )
    (net (code "233") (name "unconnected-(U10FA-IO_L23P_T3_A03_D19_14-PadN13)") (class "Default")
      (node (ref "U10F") (pin "N13") (pinfunction "IO_L23P_T3_A03_D19_14_N13") (pintype "bidirectional"))
    )
    (net (code "234") (name "unconnected-(U10FB-IO_0_15-PadJ16)") (class "Default")
      (node (ref "U10F") (pin "J16") (pinfunction "IO_0_15_J16") (pintype "bidirectional"))
    )
    (net (code "235") (name "unconnected-(U10FB-IO_25_15-PadM17)") (class "Default")
      (node (ref "U10F") (pin "M17") (pinfunction "IO_25_15_M17") (pintype "bidirectional"))
    )
    (net (code "236") (name "unconnected-(U10FB-IO_L1P_T0_AD0P_15-PadH13)") (class "Default")
      (node (ref "U10F") (pin "H13") (pinfunction "IO_L1P_T0_AD0P_15_H13") (pintype "bidirectional"))
    )
    (net (code "237") (name "unconnected-(U10FB-IO_L2N_T0_AD8N_15-PadG16)") (class "Default")
      (node (ref "U10F") (pin "G16") (pinfunction "IO_L2N_T0_AD8N_15_G16") (pintype "bidirectional"))
    )
    (net (code "238") (name "unconnected-(U10FB-IO_L2P_T0_AD8P_15-PadG15)") (class "Default")
      (node (ref "U10F") (pin "G15") (pinfunction "IO_L2P_T0_AD8P_15_G15") (pintype "bidirectional"))
    )
    (net (code "239") (name "unconnected-(U10FB-IO_L3N_T0_DQS_AD1N_15-PadH14)") (class "Default")
      (node (ref "U10F") (pin "H14") (pinfunction "IO_L3N_T0_DQS_AD1N_15_H14") (pintype "bidirectional"))
    )
    (net (code "240") (name "unconnected-(U10FB-IO_L3P_T0_DQS_AD1P_15-PadJ14)") (class "Default")
      (node (ref "U10F") (pin "J14") (pinfunction "IO_L3P_T0_DQS_AD1P_15_J14") (pintype "bidirectional"))
    )
    (net (code "241") (name "unconnected-(U10FB-IO_L4N_T0_15-PadG18)") (class "Default")
      (node (ref "U10F") (pin "G18") (pinfunction "IO_L4N_T0_15_G18") (pintype "bidirectional"))
    )
    (net (code "242") (name "unconnected-(U10FB-IO_L4P_T0_15-PadG17)") (class "Default")
      (node (ref "U10F") (pin "G17") (pinfunction "IO_L4P_T0_15_G17") (pintype "bidirectional"))
    )
    (net (code "243") (name "unconnected-(U10FB-IO_L5N_T0_AD9N_15-PadH15)") (class "Default")
      (node (ref "U10F") (pin "H15") (pinfunction "IO_L5N_T0_AD9N_15_H15") (pintype "bidirectional"))
    )
    (net (code "244") (name "unconnected-(U10FB-IO_L5P_T0_AD9P_15-PadJ15)") (class "Default")
      (node (ref "U10F") (pin "J15") (pinfunction "IO_L5P_T0_AD9P_15_J15") (pintype "bidirectional"))
    )
    (net (code "245") (name "unconnected-(U10FB-IO_L6P_T0_15-PadH17)") (class "Default")
      (node (ref "U10F") (pin "H17") (pinfunction "IO_L6P_T0_15_H17") (pintype "bidirectional"))
    )
    (net (code "246") (name "unconnected-(U10FB-IO_L8P_T1_AD10P_15-PadH20)") (class "Default")
      (node (ref "U10F") (pin "H20") (pinfunction "IO_L8P_T1_AD10P_15_H20") (pintype "bidirectional"))
    )
    (net (code "247") (name "unconnected-(U10FB-IO_L12N_T1_MRCC_15-PadH19)") (class "Default")
      (node (ref "U10F") (pin "H19") (pinfunction "IO_L12N_T1_MRCC_15_H19") (pintype "bidirectional"))
    )
    (net (code "248") (name "unconnected-(U10FB-IO_L13N_T2_MRCC_15-PadK19)") (class "Default")
      (node (ref "U10F") (pin "K19") (pinfunction "IO_L13N_T2_MRCC_15_K19") (pintype "bidirectional"))
    )
    (net (code "249") (name "unconnected-(U10FB-IO_L16N_T2_A27_15-PadL18)") (class "Default")
      (node (ref "U10F") (pin "L18") (pinfunction "IO_L16N_T2_A27_15_L18") (pintype "bidirectional"))
    )
    (net (code "250") (name "unconnected-(U10FB-IO_L16P_T2_A28_15-PadM18)") (class "Default")
      (node (ref "U10F") (pin "M18") (pinfunction "IO_L16P_T2_A28_15_M18") (pintype "bidirectional"))
    )
    (net (code "251") (name "unconnected-(U10FB-IO_L17N_T2_A25_15-PadN19)") (class "Default")
      (node (ref "U10F") (pin "N19") (pinfunction "IO_L17N_T2_A25_15_N19") (pintype "bidirectional"))
    )
    (net (code "252") (name "unconnected-(U10FB-IO_L17P_T2_A26_15-PadN18)") (class "Default")
      (node (ref "U10F") (pin "N18") (pinfunction "IO_L17P_T2_A26_15_N18") (pintype "bidirectional"))
    )
    (net (code "253") (name "unconnected-(U10FB-IO_L18N_T2_A23_15-PadM20)") (class "Default")
      (node (ref "U10F") (pin "M20") (pinfunction "IO_L18N_T2_A23_15_M20") (pintype "bidirectional"))
    )
    (net (code "254") (name "unconnected-(U10FB-IO_L19P_T3_A22_15-PadK13)") (class "Default")
      (node (ref "U10F") (pin "K13") (pinfunction "IO_L19P_T3_A22_15_K13") (pintype "bidirectional"))
    )
    (net (code "255") (name "unconnected-(U10FB-IO_L21N_T3_DQS_A18_15-PadJ17)") (class "Default")
      (node (ref "U10F") (pin "J17") (pinfunction "IO_L21N_T3_DQS_A18_15_J17") (pintype "bidirectional"))
    )
    (net (code "256") (name "unconnected-(U10FB-IO_L21P_T3_DQS_15-PadK17)") (class "Default")
      (node (ref "U10F") (pin "K17") (pinfunction "IO_L21P_T3_DQS_15_K17") (pintype "bidirectional"))
    )
    (net (code "257") (name "unconnected-(U10FB-IO_L23N_T3_FWE_B_15-PadK16)") (class "Default")
      (node (ref "U10F") (pin "K16") (pinfunction "IO_L23N_T3_FWE_B_15_K16") (pintype "bidirectional"))
    )
    (net (code "258") (name "unconnected-(U10FB-IO_L24P_T3_RS1_15-PadM15)") (class "Default")
      (node (ref "U10F") (pin "M15") (pinfunction "IO_L24P_T3_RS1_15_M15") (pintype "bidirectional"))
    )
    (net (code "259") (name "unconnected-(U10FC-IO_0_16-PadF15)") (class "Default")
      (node (ref "U10F") (pin "F15") (pinfunction "IO_0_16_F15") (pintype "bidirectional"))
    )
    (net (code "260") (name "unconnected-(U10FC-IO_L2N_T0_16-PadE17)") (class "Default")
      (node (ref "U10F") (pin "E17") (pinfunction "IO_L2N_T0_16_E17") (pintype "bidirectional"))
    )
    (net (code "261") (name "unconnected-(U10FC-IO_L5N_T0_16-PadD16)") (class "Default")
      (node (ref "U10F") (pin "D16") (pinfunction "IO_L5N_T0_16_D16") (pintype "bidirectional"))
    )
    (net (code "262") (name "unconnected-(U10FC-IO_L5P_T0_16-PadE16)") (class "Default")
      (node (ref "U10F") (pin "E16") (pinfunction "IO_L5P_T0_16_E16") (pintype "bidirectional"))
    )
    (net (code "263") (name "unconnected-(U10FC-IO_L6P_T0_16-PadD14)") (class "Default")
      (node (ref "U10F") (pin "D14") (pinfunction "IO_L6P_T0_16_D14") (pintype "bidirectional"))
    )
    (net (code "264") (name "unconnected-(U10FC-IO_L8P_T1_16-PadC13)") (class "Default")
      (node (ref "U10F") (pin "C13") (pinfunction "IO_L8P_T1_16_C13") (pintype "bidirectional"))
    )
    (net (code "265") (name "unconnected-(U10FC-IO_L15P_T2_DQS_16-PadF18)") (class "Default")
      (node (ref "U10F") (pin "F18") (pinfunction "IO_L15P_T2_DQS_16_F18") (pintype "bidirectional"))
    )
    (net (code "266") (name "unconnected-(U10FC-IO_L18P_T2_16-PadF19)") (class "Default")
      (node (ref "U10F") (pin "F19") (pinfunction "IO_L18P_T2_16_F19") (pintype "bidirectional"))
    )
    (net (code "267") (name "unconnected-(U10FC-IO_L23P_T3_16-PadE21)") (class "Default")
      (node (ref "U10F") (pin "E21") (pinfunction "IO_L23P_T3_16_E21") (pintype "bidirectional"))
    )
    (net (code "268") (name "unconnected-(U10FD-IO_0_34-PadT3)") (class "Default")
      (node (ref "U10F") (pin "T3") (pinfunction "IO_0_34_T3") (pintype "bidirectional"))
    )
    (net (code "269") (name "unconnected-(U10FD-IO_25_34-PadU7)") (class "Default")
      (node (ref "U10F") (pin "U7") (pinfunction "IO_25_34_U7") (pintype "bidirectional"))
    )
    (net (code "270") (name "unconnected-(U10FD-IO_L1N_T0_34-PadU1)") (class "Default")
      (node (ref "U10F") (pin "U1") (pinfunction "IO_L1N_T0_34_U1") (pintype "bidirectional"))
    )
    (net (code "271") (name "unconnected-(U10FD-IO_L1P_T0_34-PadT1)") (class "Default")
      (node (ref "U10F") (pin "T1") (pinfunction "IO_L1P_T0_34_T1") (pintype "bidirectional"))
    )
    (net (code "272") (name "unconnected-(U10FD-IO_L2P_T0_34-PadU2)") (class "Default")
      (node (ref "U10F") (pin "U2") (pinfunction "IO_L2P_T0_34_U2") (pintype "bidirectional"))
    )
    (net (code "273") (name "unconnected-(U10FD-IO_L4P_T0_34-PadW2)") (class "Default")
      (node (ref "U10F") (pin "W2") (pinfunction "IO_L4P_T0_34_W2") (pintype "bidirectional"))
    )
    (net (code "274") (name "unconnected-(U10FD-IO_L5P_T0_34-PadW1)") (class "Default")
      (node (ref "U10F") (pin "W1") (pinfunction "IO_L5P_T0_34_W1") (pintype "bidirectional"))
    )
    (net (code "275") (name "unconnected-(U10FD-IO_L6P_T0_34-PadU3)") (class "Default")
      (node (ref "U10F") (pin "U3") (pinfunction "IO_L6P_T0_34_U3") (pintype "bidirectional"))
    )
    (net (code "276") (name "unconnected-(U10FD-IO_L10P_T1_34-PadAA5)") (class "Default")
      (node (ref "U10F") (pin "AA5") (pinfunction "IO_L10P_T1_34_AA5") (pintype "bidirectional"))
    )
    (net (code "277") (name "unconnected-(U10FD-IO_L11N_T1_SRCC_34-PadAA4)") (class "Default")
      (node (ref "U10F") (pin "AA4") (pinfunction "IO_L11N_T1_SRCC_34_AA4") (pintype "bidirectional"))
    )
    (net (code "278") (name "unconnected-(U10FD-IO_L11P_T1_SRCC_34-PadY4)") (class "Default")
      (node (ref "U10F") (pin "Y4") (pinfunction "IO_L11P_T1_SRCC_34_Y4") (pintype "bidirectional"))
    )
    (net (code "279") (name "unconnected-(U10FD-IO_L13N_T2_MRCC_34-PadT4)") (class "Default")
      (node (ref "U10F") (pin "T4") (pinfunction "IO_L13N_T2_MRCC_34_T4") (pintype "bidirectional"))
    )
    (net (code "280") (name "unconnected-(U10FD-IO_L13P_T2_MRCC_34-PadR4)") (class "Default")
      (node (ref "U10F") (pin "R4") (pinfunction "IO_L13P_T2_MRCC_34_R4") (pintype "bidirectional"))
    )
    (net (code "281") (name "unconnected-(U10FD-IO_L14P_T2_SRCC_34-PadT5)") (class "Default")
      (node (ref "U10F") (pin "T5") (pinfunction "IO_L14P_T2_SRCC_34_T5") (pintype "bidirectional"))
    )
    (net (code "282") (name "unconnected-(U10FD-IO_L17N_T2_34-PadT6)") (class "Default")
      (node (ref "U10F") (pin "T6") (pinfunction "IO_L17N_T2_34_T6") (pintype "bidirectional"))
    )
    (net (code "283") (name "unconnected-(U10FD-IO_L17P_T2_34-PadR6)") (class "Default")
      (node (ref "U10F") (pin "R6") (pinfunction "IO_L17P_T2_34_R6") (pintype "bidirectional"))
    )
    (net (code "284") (name "unconnected-(U10FD-IO_L18N_T2_34-PadAA6)") (class "Default")
      (node (ref "U10F") (pin "AA6") (pinfunction "IO_L18N_T2_34_AA6") (pintype "bidirectional"))
    )
    (net (code "285") (name "unconnected-(U10FD-IO_L18P_T2_34-PadY6)") (class "Default")
      (node (ref "U10F") (pin "Y6") (pinfunction "IO_L18P_T2_34_Y6") (pintype "bidirectional"))
    )
    (net (code "286") (name "unconnected-(U10FD-IO_L20N_T3_34-PadAB6)") (class "Default")
      (node (ref "U10F") (pin "AB6") (pinfunction "IO_L20N_T3_34_AB6") (pintype "bidirectional"))
    )
    (net (code "287") (name "unconnected-(U10FD-IO_L20P_T3_34-PadAB7)") (class "Default")
      (node (ref "U10F") (pin "AB7") (pinfunction "IO_L20P_T3_34_AB7") (pintype "bidirectional"))
    )
    (net (code "288") (name "unconnected-(U10FD-IO_L22N_T3_34-PadAB8)") (class "Default")
      (node (ref "U10F") (pin "AB8") (pinfunction "IO_L22N_T3_34_AB8") (pintype "bidirectional"))
    )
    (net (code "289") (name "unconnected-(U10FD-IO_L22P_T3_34-PadAA8)") (class "Default")
      (node (ref "U10F") (pin "AA8") (pinfunction "IO_L22P_T3_34_AA8") (pintype "bidirectional"))
    )
    (net (code "290") (name "unconnected-(U10FE-IO_0_35-PadF4)") (class "Default")
      (node (ref "U10F") (pin "F4") (pinfunction "IO_0_35_F4") (pintype "bidirectional"))
    )
    (net (code "291") (name "unconnected-(U10FE-IO_25_35-PadL6)") (class "Default")
      (node (ref "U10F") (pin "L6") (pinfunction "IO_25_35_L6") (pintype "bidirectional"))
    )
    (net (code "292") (name "unconnected-(U10FE-IO_L12N_T1_MRCC_35-PadG4)") (class "Default")
      (node (ref "U10F") (pin "G4") (pinfunction "IO_L12N_T1_MRCC_35_G4") (pintype "bidirectional"))
    )
    (net (code "293") (name "unconnected-(U10FE-IO_L18N_T2_35-PadL4)") (class "Default")
      (node (ref "U10F") (pin "L4") (pinfunction "IO_L18N_T2_35_L4") (pintype "bidirectional"))
    )
    (net (code "294") (name "unconnected-(U10FL-NC-PadAA9)") (class "Default")
      (node (ref "U10F") (pin "AA9") (pinfunction "NC_AA9") (pintype "passive"))
    )
    (net (code "295") (name "unconnected-(U10FL-NC-PadAA10)") (class "Default")
      (node (ref "U10F") (pin "AA10") (pinfunction "NC_AA10") (pintype "passive"))
    )
    (net (code "296") (name "unconnected-(U10FL-NC-PadAA11)") (class "Default")
      (node (ref "U10F") (pin "AA11") (pinfunction "NC_AA11") (pintype "passive"))
    )
    (net (code "297") (name "unconnected-(U10FL-NC-PadAA13)") (class "Default")
      (node (ref "U10F") (pin "AA13") (pinfunction "NC_AA13") (pintype "passive"))
    )
    (net (code "298") (name "unconnected-(U10FL-NC-PadAA14)") (class "Default")
      (node (ref "U10F") (pin "AA14") (pinfunction "NC_AA14") (pintype "passive"))
    )
    (net (code "299") (name "unconnected-(U10FL-NC-PadAA15)") (class "Default")
      (node (ref "U10F") (pin "AA15") (pinfunction "NC_AA15") (pintype "passive"))
    )
    (net (code "300") (name "unconnected-(U10FL-NC-PadAA16)") (class "Default")
      (node (ref "U10F") (pin "AA16") (pinfunction "NC_AA16") (pintype "passive"))
    )
    (net (code "301") (name "unconnected-(U10FL-NC-PadAB10)") (class "Default")
      (node (ref "U10F") (pin "AB10") (pinfunction "NC_AB10") (pintype "passive"))
    )
    (net (code "302") (name "unconnected-(U10FL-NC-PadAB11)") (class "Default")
      (node (ref "U10F") (pin "AB11") (pinfunction "NC_AB11") (pintype "passive"))
    )
    (net (code "303") (name "unconnected-(U10FL-NC-PadAB12)") (class "Default")
      (node (ref "U10F") (pin "AB12") (pinfunction "NC_AB12") (pintype "passive"))
    )
    (net (code "304") (name "unconnected-(U10FL-NC-PadAB13)") (class "Default")
      (node (ref "U10F") (pin "AB13") (pinfunction "NC_AB13") (pintype "passive"))
    )
    (net (code "305") (name "unconnected-(U10FL-NC-PadAB15)") (class "Default")
      (node (ref "U10F") (pin "AB15") (pinfunction "NC_AB15") (pintype "passive"))
    )
    (net (code "306") (name "unconnected-(U10FL-NC-PadAB16)") (class "Default")
      (node (ref "U10F") (pin "AB16") (pinfunction "NC_AB16") (pintype "passive"))
    )
    (net (code "307") (name "unconnected-(U10FL-NC-PadAB17)") (class "Default")
      (node (ref "U10F") (pin "AB17") (pinfunction "NC_AB17") (pintype "passive"))
    )
    (net (code "308") (name "unconnected-(U10FL-NC-PadT14)") (class "Default")
      (node (ref "U10F") (pin "T14") (pinfunction "NC_T14") (pintype "passive"))
    )
    (net (code "309") (name "unconnected-(U10FL-NC-PadT15)") (class "Default")
      (node (ref "U10F") (pin "T15") (pinfunction "NC_T15") (pintype "passive"))
    )
    (net (code "310") (name "unconnected-(U10FL-NC-PadT16)") (class "Default")
      (node (ref "U10F") (pin "T16") (pinfunction "NC_T16") (pintype "passive"))
    )
    (net (code "311") (name "unconnected-(U10FL-NC-PadU15)") (class "Default")
      (node (ref "U10F") (pin "U15") (pinfunction "NC_U15") (pintype "passive"))
    )
    (net (code "312") (name "unconnected-(U10FL-NC-PadU16)") (class "Default")
      (node (ref "U10F") (pin "U16") (pinfunction "NC_U16") (pintype "passive"))
    )
    (net (code "313") (name "unconnected-(U10FL-NC-PadV10)") (class "Default")
      (node (ref "U10F") (pin "V10") (pinfunction "NC_V10") (pintype "passive"))
    )
    (net (code "314") (name "unconnected-(U10FL-NC-PadV13)") (class "Default")
      (node (ref "U10F") (pin "V13") (pinfunction "NC_V13") (pintype "passive"))
    )
    (net (code "315") (name "unconnected-(U10FL-NC-PadV14)") (class "Default")
      (node (ref "U10F") (pin "V14") (pinfunction "NC_V14") (pintype "passive"))
    )
    (net (code "316") (name "unconnected-(U10FL-NC-PadV15)") (class "Default")
      (node (ref "U10F") (pin "V15") (pinfunction "NC_V15") (pintype "passive"))
    )
    (net (code "317") (name "unconnected-(U10FL-NC-PadW10)") (class "Default")
      (node (ref "U10F") (pin "W10") (pinfunction "NC_W10") (pintype "passive"))
    )
    (net (code "318") (name "unconnected-(U10FL-NC-PadW11)") (class "Default")
      (node (ref "U10F") (pin "W11") (pinfunction "NC_W11") (pintype "passive"))
    )
    (net (code "319") (name "unconnected-(U10FL-NC-PadW12)") (class "Default")
      (node (ref "U10F") (pin "W12") (pinfunction "NC_W12") (pintype "passive"))
    )
    (net (code "320") (name "unconnected-(U10FL-NC-PadW14)") (class "Default")
      (node (ref "U10F") (pin "W14") (pinfunction "NC_W14") (pintype "passive"))
    )
    (net (code "321") (name "unconnected-(U10FL-NC-PadW15)") (class "Default")
      (node (ref "U10F") (pin "W15") (pinfunction "NC_W15") (pintype "passive"))
    )
    (net (code "322") (name "unconnected-(U10FL-NC-PadW16)") (class "Default")
      (node (ref "U10F") (pin "W16") (pinfunction "NC_W16") (pintype "passive"))
    )
    (net (code "323") (name "unconnected-(U10FL-NC-PadY11)") (class "Default")
      (node (ref "U10F") (pin "Y11") (pinfunction "NC_Y11") (pintype "passive"))
    )
    (net (code "324") (name "unconnected-(U10FL-NC-PadY12)") (class "Default")
      (node (ref "U10F") (pin "Y12") (pinfunction "NC_Y12") (pintype "passive"))
    )
    (net (code "325") (name "unconnected-(U10FL-NC-PadY13)") (class "Default")
      (node (ref "U10F") (pin "Y13") (pinfunction "NC_Y13") (pintype "passive"))
    )
    (net (code "326") (name "unconnected-(U10FL-NC-PadY14)") (class "Default")
      (node (ref "U10F") (pin "Y14") (pinfunction "NC_Y14") (pintype "passive"))
    )
    (net (code "327") (name "unconnected-(U10FL-NC-PadY16)") (class "Default")
      (node (ref "U10F") (pin "Y16") (pinfunction "NC_Y16") (pintype "passive"))
    )
    (net (code "328") (name "unconnected-(U10FL-NC-PadY17)") (class "Default")
      (node (ref "U10F") (pin "Y17") (pinfunction "NC_Y17") (pintype "passive"))
    )
  )
)
